# Avalon16.net
KiCad netlist of a schematic drawn in EAGLE
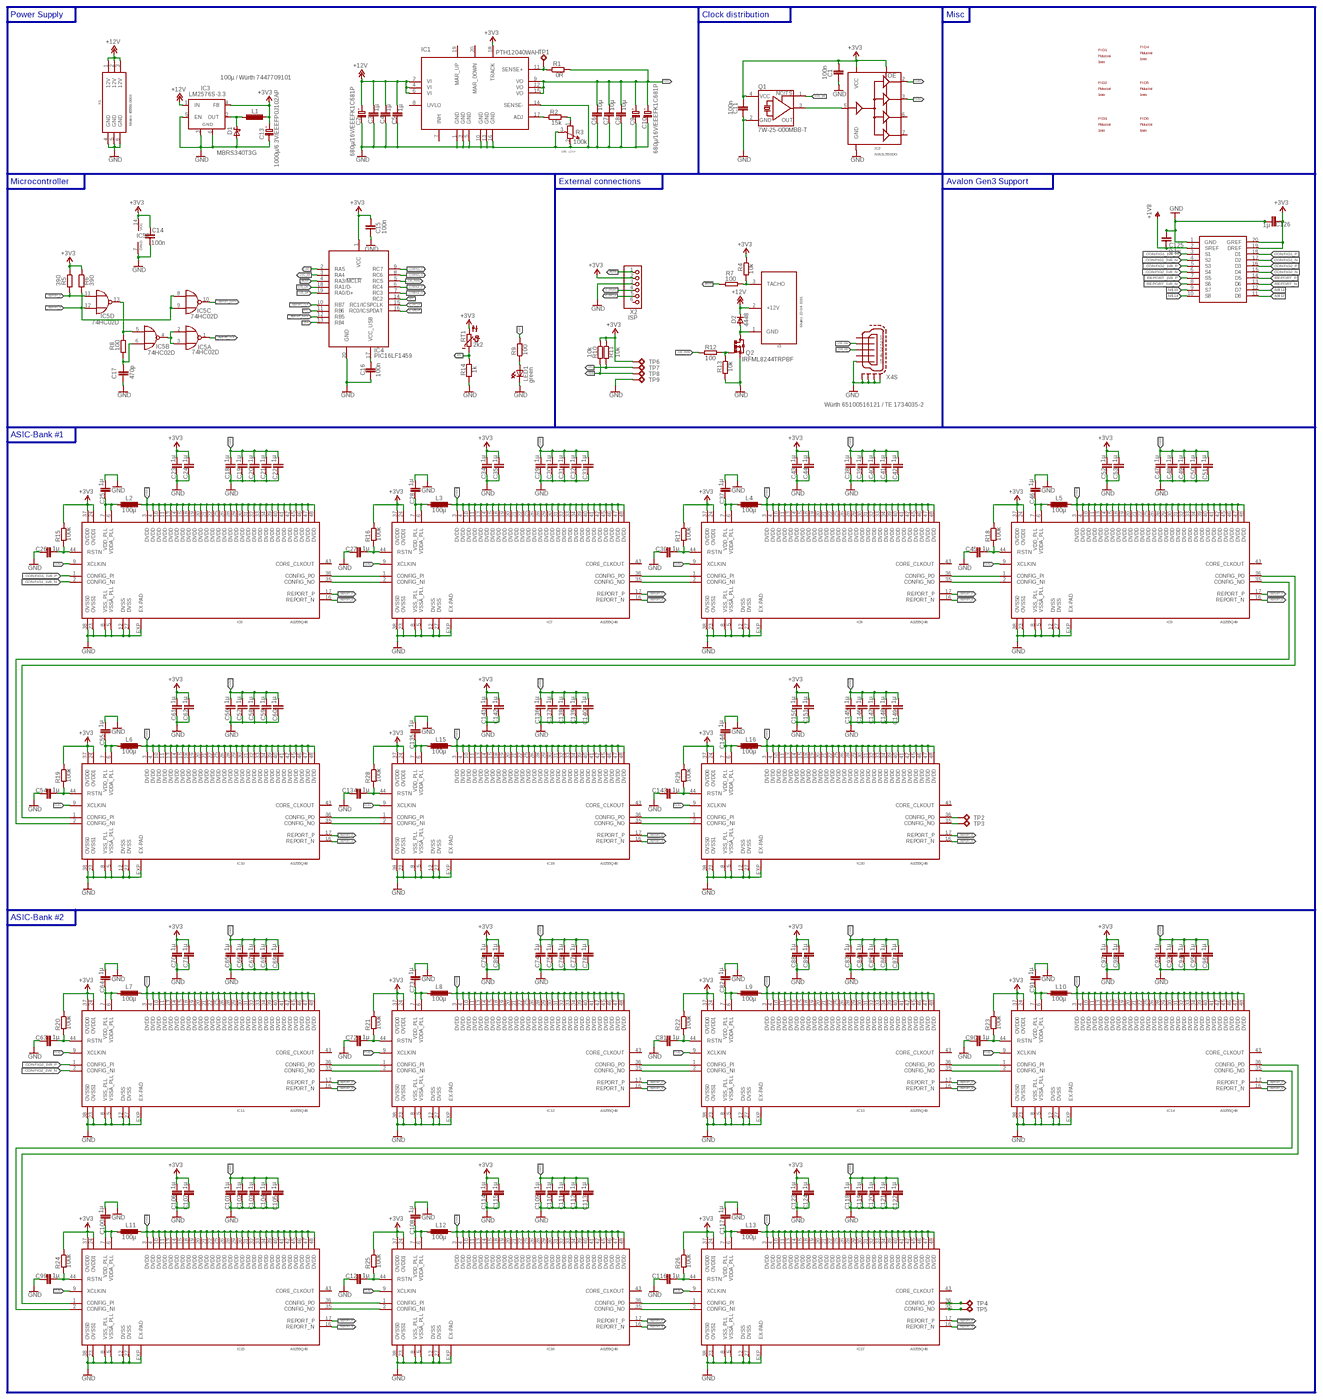
[diagram p0: schematic, sheet 1, overview]
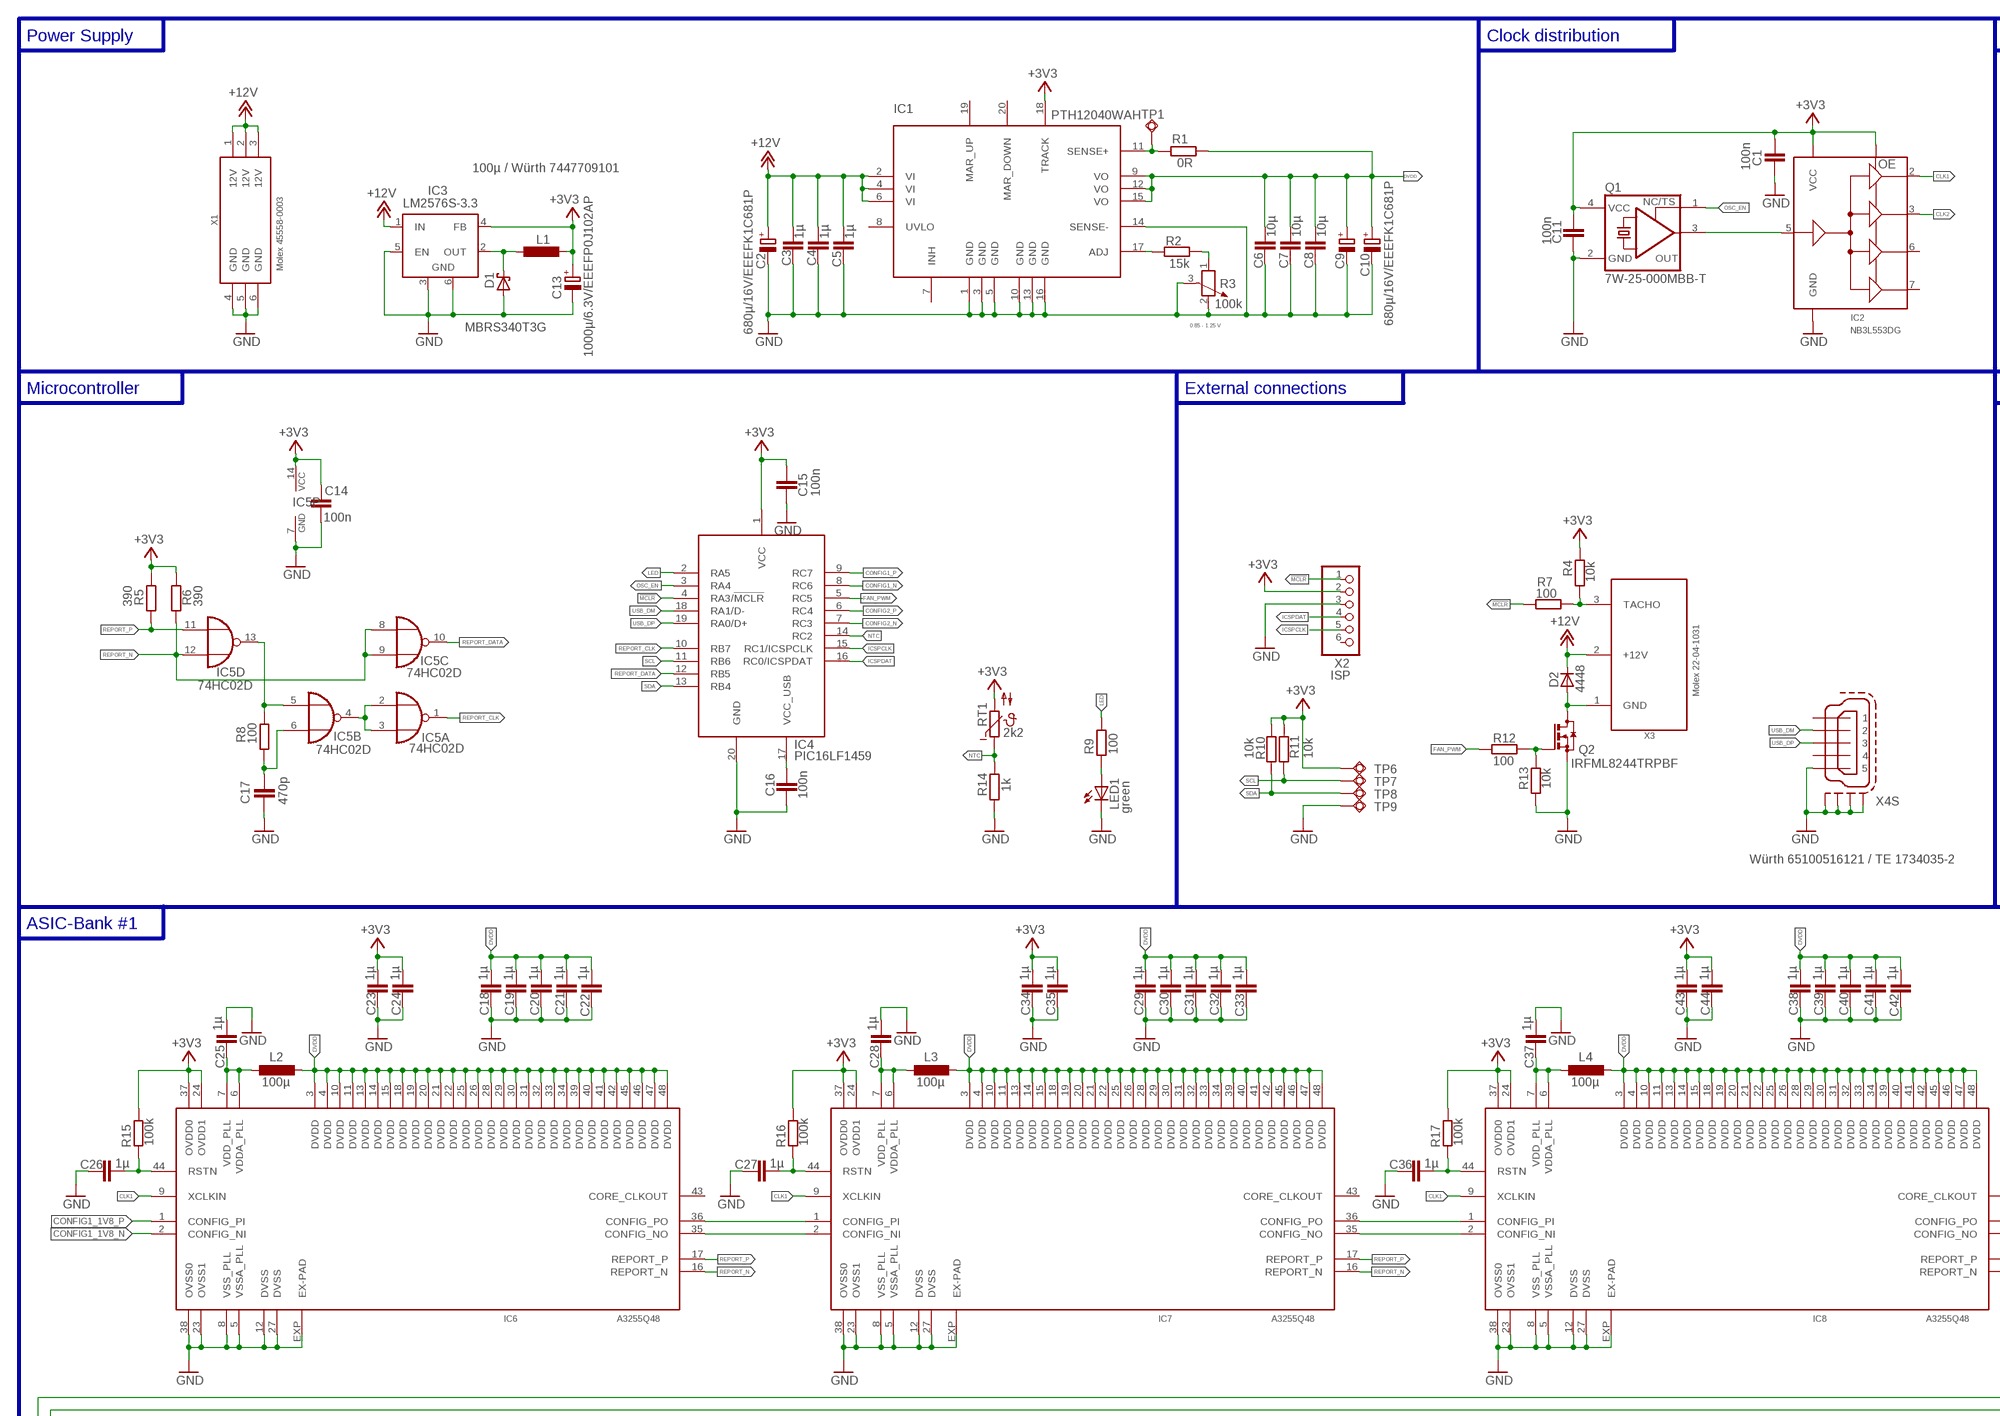
[diagram p1: schematic, sheet 1, part 1 of 4]
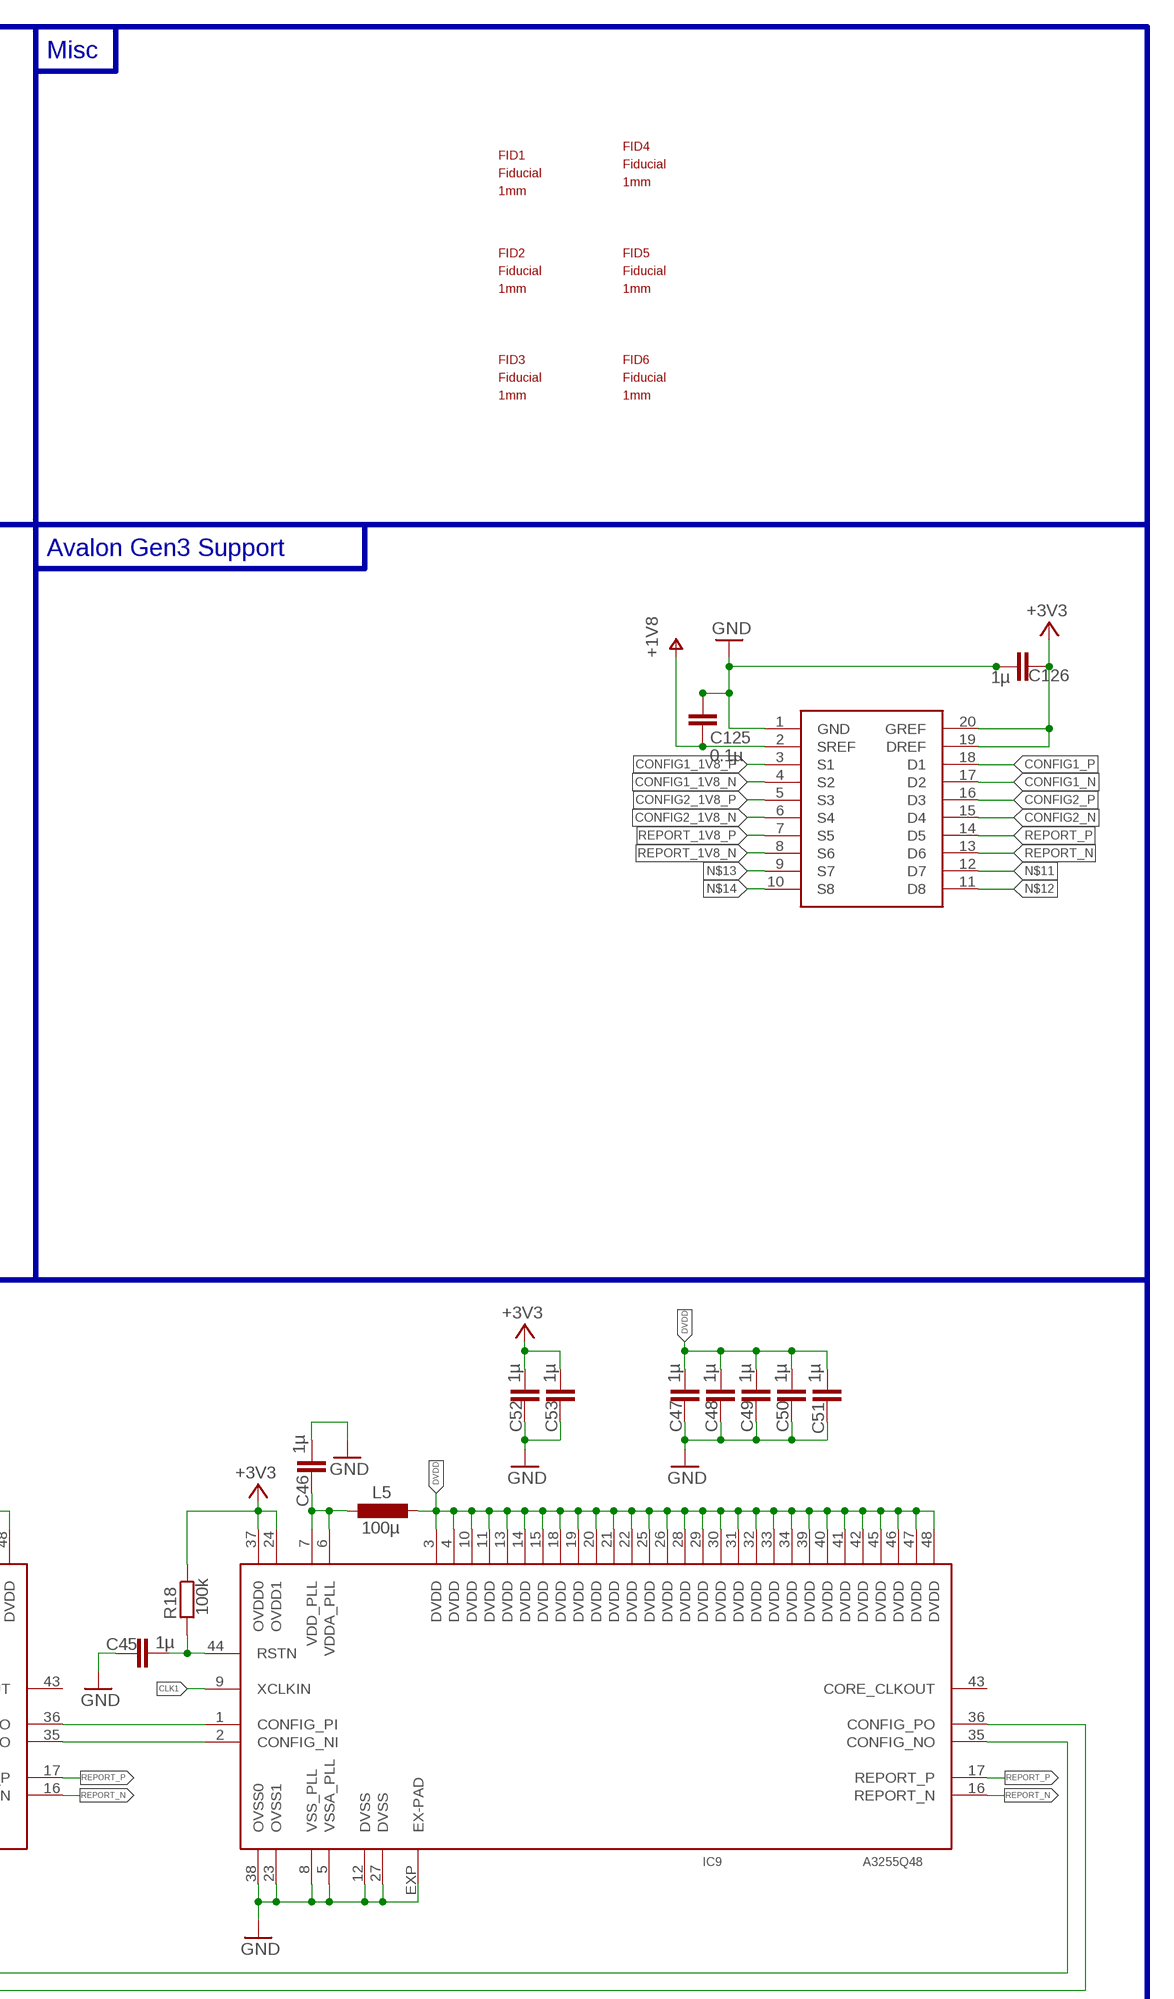
[diagram p2: schematic, sheet 1, part 2 of 4]
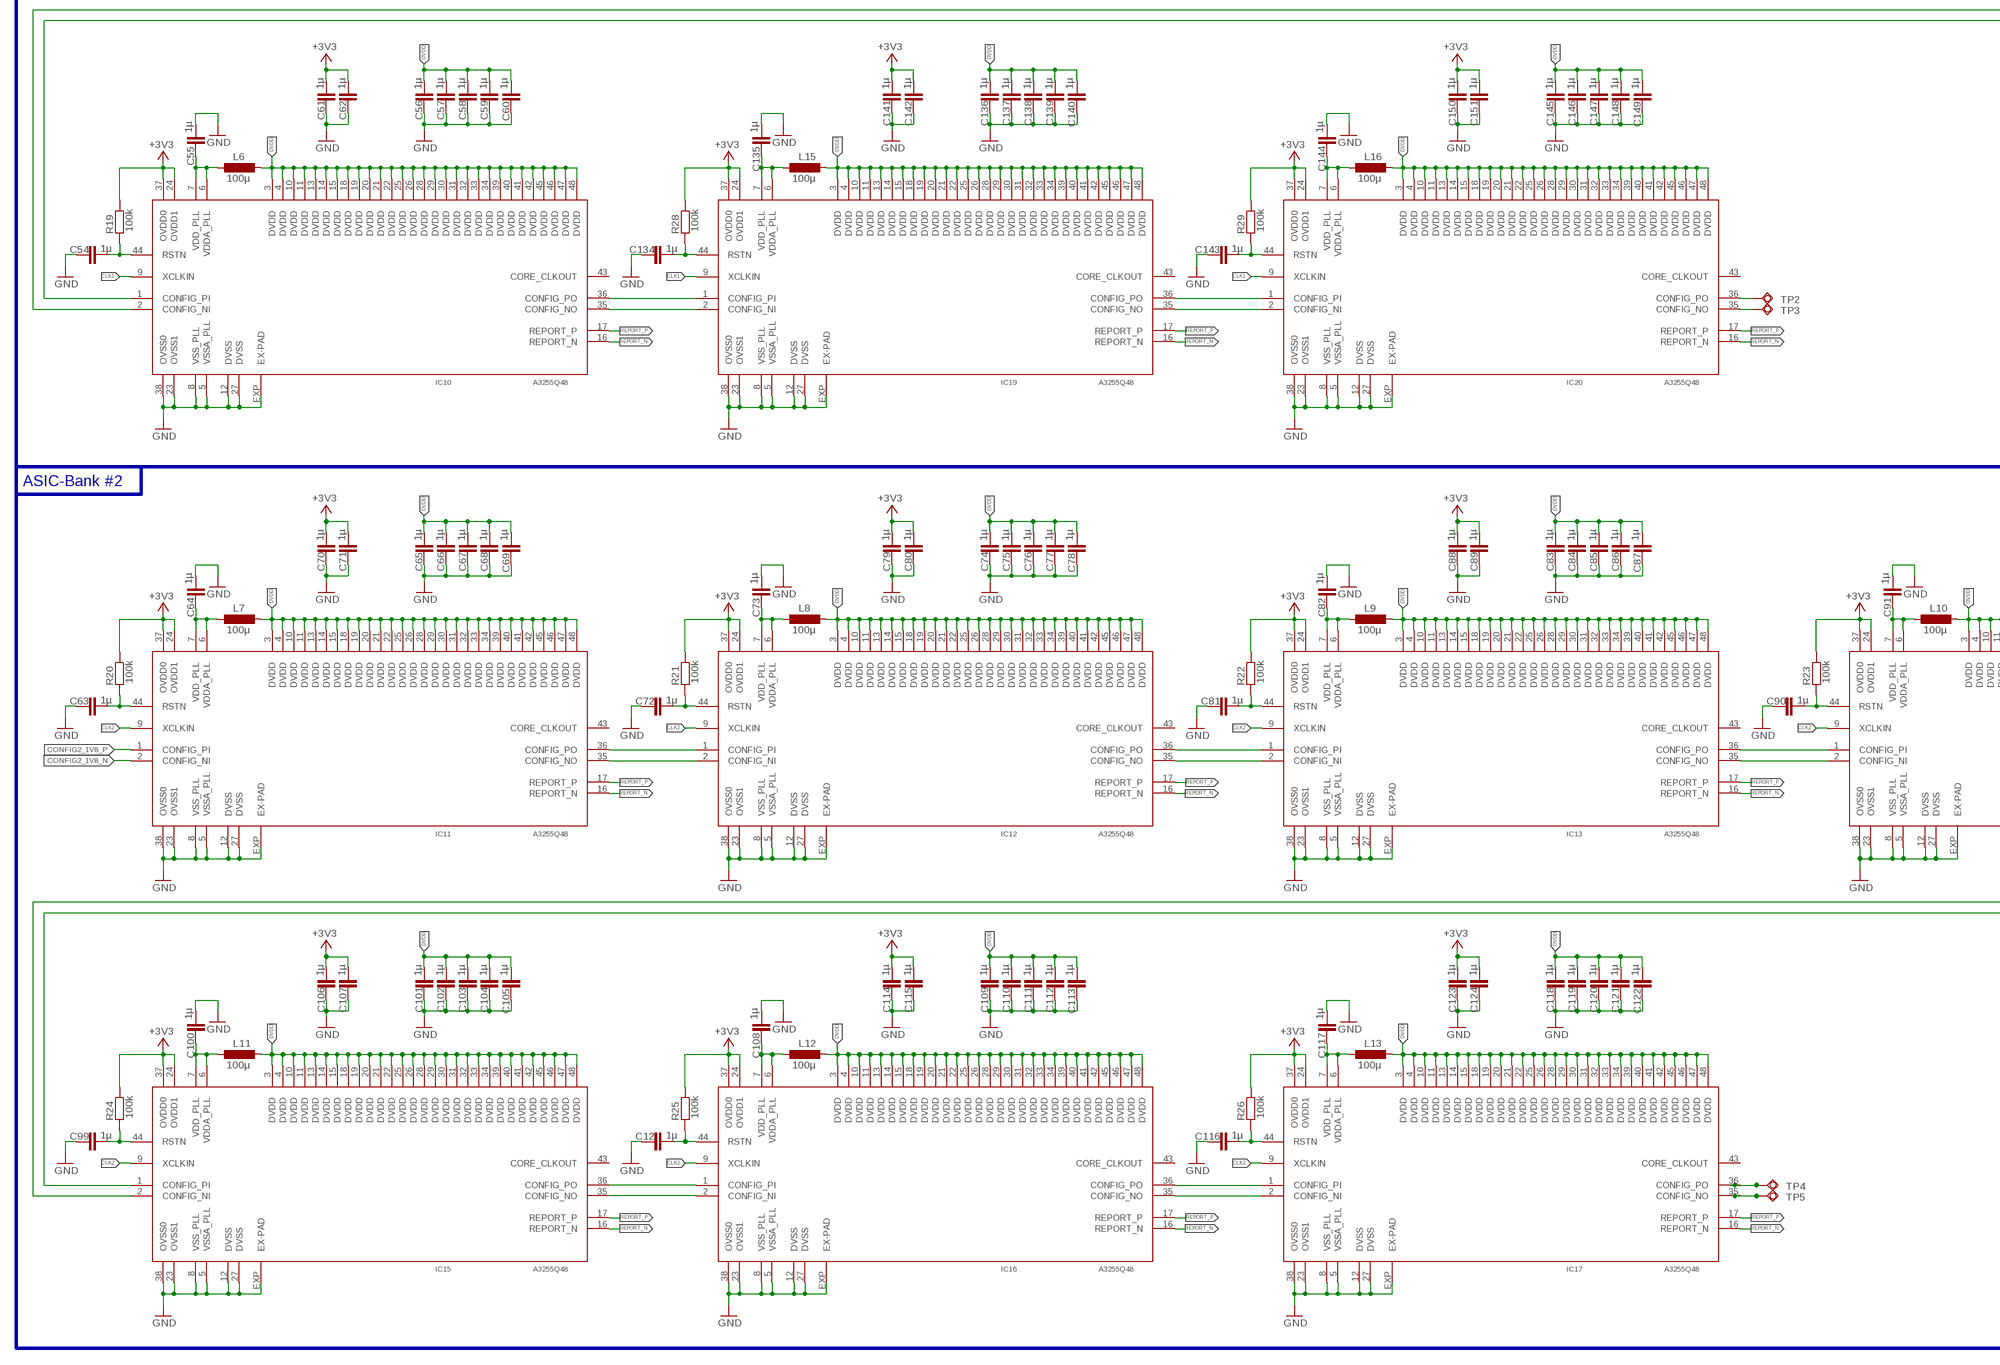
[diagram p3: schematic, sheet 1, part 3 of 4]
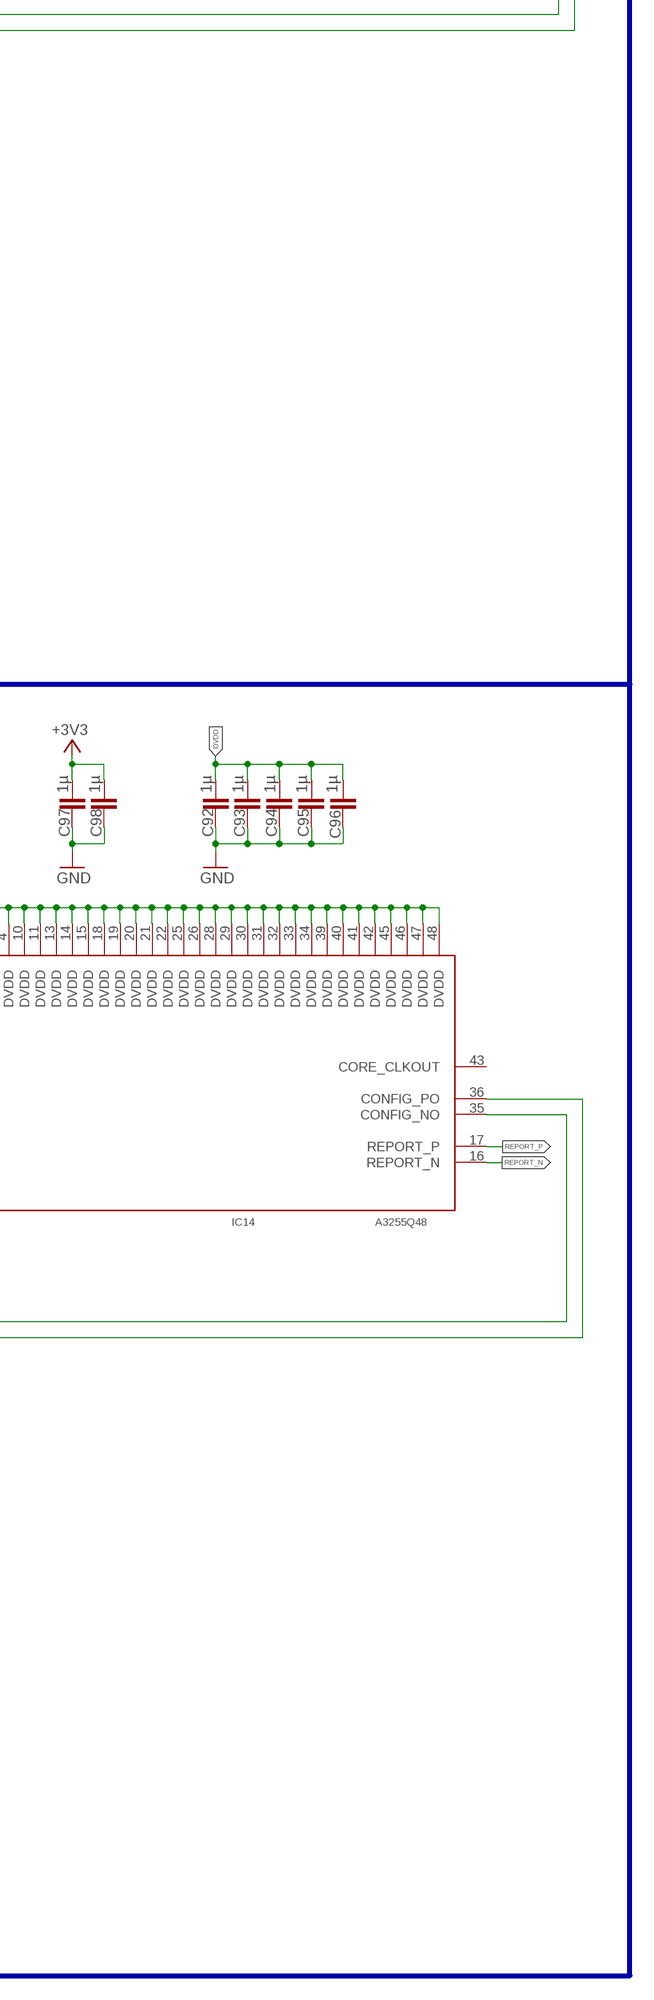
[diagram p4: schematic, sheet 1, part 4 of 4]

(export (version "E")
  (design (tool "Eeschema 10.0.6"))
  (components
    (comp (ref "C1")
      (value "100n")
      (footprint "eagle-import:C0805")
      (libsource (lib "eagle-import") (part "C-EUC0805"))
    )
    (comp (ref "C2")
      (value "680µ/16V/EEEFK1C681P")
      (footprint "eagle-import:PANASONIC_G")
      (libsource (lib "eagle-import") (part "CPOL-EUG"))
    )
    (comp (ref "C3")
      (value "1µ")
      (footprint "eagle-import:C0805")
      (libsource (lib "eagle-import") (part "C-EUC0805"))
    )
    (comp (ref "C4")
      (value "1µ")
      (footprint "eagle-import:C0805")
      (libsource (lib "eagle-import") (part "C-EUC0805"))
    )
    (comp (ref "C5")
      (value "1µ")
      (footprint "eagle-import:C0805")
      (libsource (lib "eagle-import") (part "C-EUC0805"))
    )
    (comp (ref "C6")
      (value "10µ")
      (footprint "eagle-import:C0805")
      (libsource (lib "eagle-import") (part "C-EUC0805"))
    )
    (comp (ref "C7")
      (value "10µ")
      (footprint "eagle-import:C0805")
      (libsource (lib "eagle-import") (part "C-EUC0805"))
    )
    (comp (ref "C8")
      (value "10µ")
      (footprint "eagle-import:C0805")
      (libsource (lib "eagle-import") (part "C-EUC0805"))
    )
    (comp (ref "C9")
      (value "680µ/16V/EEEFK1C681P")
      (footprint "eagle-import:PANASONIC_G")
      (libsource (lib "eagle-import") (part "CPOL-EUG"))
    )
    (comp (ref "C10")
      (value "680µ/16V/EEEFK1C681P")
      (footprint "eagle-import:PANASONIC_G")
      (libsource (lib "eagle-import") (part "CPOL-EUG"))
    )
    (comp (ref "C11")
      (value "100n")
      (footprint "eagle-import:C0805")
      (libsource (lib "eagle-import") (part "C-EUC0805"))
    )
    (comp (ref "C12")
      (value "1µ")
      (footprint "eagle-import:C0805")
      (libsource (lib "eagle-import") (part "C-EUC0805"))
    )
    (comp (ref "C13")
      (value "1000µ/6.3V/EEEFP0J102AP")
      (footprint "eagle-import:PANASONIC_F")
      (libsource (lib "eagle-import") (part "CPOL-EUF"))
    )
    (comp (ref "C14")
      (value "100n")
      (footprint "eagle-import:C0805")
      (libsource (lib "eagle-import") (part "C-EUC0805"))
    )
    (comp (ref "C15")
      (value "100n")
      (footprint "eagle-import:C0805")
      (libsource (lib "eagle-import") (part "C-EUC0805"))
    )
    (comp (ref "C16")
      (value "100n")
      (footprint "eagle-import:C0805")
      (libsource (lib "eagle-import") (part "C-EUC0805"))
    )
    (comp (ref "C17")
      (value "470p")
      (footprint "eagle-import:C0805")
      (libsource (lib "eagle-import") (part "C-EUC0805"))
    )
    (comp (ref "C18")
      (value "1µ")
      (footprint "eagle-import:C0805")
      (libsource (lib "eagle-import") (part "C-EUC0805"))
    )
    (comp (ref "C19")
      (value "1µ")
      (footprint "eagle-import:C0805")
      (libsource (lib "eagle-import") (part "C-EUC0805"))
    )
    (comp (ref "C20")
      (value "1µ")
      (footprint "eagle-import:C0805")
      (libsource (lib "eagle-import") (part "C-EUC0805"))
    )
    (comp (ref "C21")
      (value "1µ")
      (footprint "eagle-import:C0805")
      (libsource (lib "eagle-import") (part "C-EUC0805"))
    )
    (comp (ref "C22")
      (value "1µ")
      (footprint "eagle-import:C0805")
      (libsource (lib "eagle-import") (part "C-EUC0805"))
    )
    (comp (ref "C23")
      (value "1µ")
      (footprint "eagle-import:C0805")
      (libsource (lib "eagle-import") (part "C-EUC0805"))
    )
    (comp (ref "C24")
      (value "1µ")
      (footprint "eagle-import:C0805")
      (libsource (lib "eagle-import") (part "C-EUC0805"))
    )
    (comp (ref "C25")
      (value "1µ")
      (footprint "eagle-import:C0805")
      (libsource (lib "eagle-import") (part "C-EUC0805"))
    )
    (comp (ref "C26")
      (value "1µ")
      (footprint "eagle-import:C0805")
      (libsource (lib "eagle-import") (part "C-EUC0805"))
    )
    (comp (ref "C27")
      (value "1µ")
      (footprint "eagle-import:C0805")
      (libsource (lib "eagle-import") (part "C-EUC0805"))
    )
    (comp (ref "C28")
      (value "1µ")
      (footprint "eagle-import:C0805")
      (libsource (lib "eagle-import") (part "C-EUC0805"))
    )
    (comp (ref "C29")
      (value "1µ")
      (footprint "eagle-import:C0805")
      (libsource (lib "eagle-import") (part "C-EUC0805"))
    )
    (comp (ref "C30")
      (value "1µ")
      (footprint "eagle-import:C0805")
      (libsource (lib "eagle-import") (part "C-EUC0805"))
    )
    (comp (ref "C31")
      (value "1µ")
      (footprint "eagle-import:C0805")
      (libsource (lib "eagle-import") (part "C-EUC0805"))
    )
    (comp (ref "C32")
      (value "1µ")
      (footprint "eagle-import:C0805")
      (libsource (lib "eagle-import") (part "C-EUC0805"))
    )
    (comp (ref "C33")
      (value "1µ")
      (footprint "eagle-import:C0805")
      (libsource (lib "eagle-import") (part "C-EUC0805"))
    )
    (comp (ref "C34")
      (value "1µ")
      (footprint "eagle-import:C0805")
      (libsource (lib "eagle-import") (part "C-EUC0805"))
    )
    (comp (ref "C35")
      (value "1µ")
      (footprint "eagle-import:C0805")
      (libsource (lib "eagle-import") (part "C-EUC0805"))
    )
    (comp (ref "C36")
      (value "1µ")
      (footprint "eagle-import:C0805")
      (libsource (lib "eagle-import") (part "C-EUC0805"))
    )
    (comp (ref "C37")
      (value "1µ")
      (footprint "eagle-import:C0805")
      (libsource (lib "eagle-import") (part "C-EUC0805"))
    )
    (comp (ref "C38")
      (value "1µ")
      (footprint "eagle-import:C0805")
      (libsource (lib "eagle-import") (part "C-EUC0805"))
    )
    (comp (ref "C39")
      (value "1µ")
      (footprint "eagle-import:C0805")
      (libsource (lib "eagle-import") (part "C-EUC0805"))
    )
    (comp (ref "C40")
      (value "1µ")
      (footprint "eagle-import:C0805")
      (libsource (lib "eagle-import") (part "C-EUC0805"))
    )
    (comp (ref "C41")
      (value "1µ")
      (footprint "eagle-import:C0805")
      (libsource (lib "eagle-import") (part "C-EUC0805"))
    )
    (comp (ref "C42")
      (value "1µ")
      (footprint "eagle-import:C0805")
      (libsource (lib "eagle-import") (part "C-EUC0805"))
    )
    (comp (ref "C43")
      (value "1µ")
      (footprint "eagle-import:C0805")
      (libsource (lib "eagle-import") (part "C-EUC0805"))
    )
    (comp (ref "C44")
      (value "1µ")
      (footprint "eagle-import:C0805")
      (libsource (lib "eagle-import") (part "C-EUC0805"))
    )
    (comp (ref "C45")
      (value "1µ")
      (footprint "eagle-import:C0805")
      (libsource (lib "eagle-import") (part "C-EUC0805"))
    )
    (comp (ref "C46")
      (value "1µ")
      (footprint "eagle-import:C0805")
      (libsource (lib "eagle-import") (part "C-EUC0805"))
    )
    (comp (ref "C47")
      (value "1µ")
      (footprint "eagle-import:C0805")
      (libsource (lib "eagle-import") (part "C-EUC0805"))
    )
    (comp (ref "C48")
      (value "1µ")
      (footprint "eagle-import:C0805")
      (libsource (lib "eagle-import") (part "C-EUC0805"))
    )
    (comp (ref "C49")
      (value "1µ")
      (footprint "eagle-import:C0805")
      (libsource (lib "eagle-import") (part "C-EUC0805"))
    )
    (comp (ref "C50")
      (value "1µ")
      (footprint "eagle-import:C0805")
      (libsource (lib "eagle-import") (part "C-EUC0805"))
    )
    (comp (ref "C51")
      (value "1µ")
      (footprint "eagle-import:C0805")
      (libsource (lib "eagle-import") (part "C-EUC0805"))
    )
    (comp (ref "C52")
      (value "1µ")
      (footprint "eagle-import:C0805")
      (libsource (lib "eagle-import") (part "C-EUC0805"))
    )
    (comp (ref "C53")
      (value "1µ")
      (footprint "eagle-import:C0805")
      (libsource (lib "eagle-import") (part "C-EUC0805"))
    )
    (comp (ref "C54")
      (value "1µ")
      (footprint "eagle-import:C0805")
      (libsource (lib "eagle-import") (part "C-EUC0805"))
    )
    (comp (ref "C55")
      (value "1µ")
      (footprint "eagle-import:C0805")
      (libsource (lib "eagle-import") (part "C-EUC0805"))
    )
    (comp (ref "C56")
      (value "1µ")
      (footprint "eagle-import:C0805")
      (libsource (lib "eagle-import") (part "C-EUC0805"))
    )
    (comp (ref "C57")
      (value "1µ")
      (footprint "eagle-import:C0805")
      (libsource (lib "eagle-import") (part "C-EUC0805"))
    )
    (comp (ref "C58")
      (value "1µ")
      (footprint "eagle-import:C0805")
      (libsource (lib "eagle-import") (part "C-EUC0805"))
    )
    (comp (ref "C59")
      (value "1µ")
      (footprint "eagle-import:C0805")
      (libsource (lib "eagle-import") (part "C-EUC0805"))
    )
    (comp (ref "C60")
      (value "1µ")
      (footprint "eagle-import:C0805")
      (libsource (lib "eagle-import") (part "C-EUC0805"))
    )
    (comp (ref "C61")
      (value "1µ")
      (footprint "eagle-import:C0805")
      (libsource (lib "eagle-import") (part "C-EUC0805"))
    )
    (comp (ref "C62")
      (value "1µ")
      (footprint "eagle-import:C0805")
      (libsource (lib "eagle-import") (part "C-EUC0805"))
    )
    (comp (ref "C63")
      (value "1µ")
      (footprint "eagle-import:C0805")
      (libsource (lib "eagle-import") (part "C-EUC0805"))
    )
    (comp (ref "C64")
      (value "1µ")
      (footprint "eagle-import:C0805")
      (libsource (lib "eagle-import") (part "C-EUC0805"))
    )
    (comp (ref "C65")
      (value "1µ")
      (footprint "eagle-import:C0805")
      (libsource (lib "eagle-import") (part "C-EUC0805"))
    )
    (comp (ref "C66")
      (value "1µ")
      (footprint "eagle-import:C0805")
      (libsource (lib "eagle-import") (part "C-EUC0805"))
    )
    (comp (ref "C67")
      (value "1µ")
      (footprint "eagle-import:C0805")
      (libsource (lib "eagle-import") (part "C-EUC0805"))
    )
    (comp (ref "C68")
      (value "1µ")
      (footprint "eagle-import:C0805")
      (libsource (lib "eagle-import") (part "C-EUC0805"))
    )
    (comp (ref "C69")
      (value "1µ")
      (footprint "eagle-import:C0805")
      (libsource (lib "eagle-import") (part "C-EUC0805"))
    )
    (comp (ref "C70")
      (value "1µ")
      (footprint "eagle-import:C0805")
      (libsource (lib "eagle-import") (part "C-EUC0805"))
    )
    (comp (ref "C71")
      (value "1µ")
      (footprint "eagle-import:C0805")
      (libsource (lib "eagle-import") (part "C-EUC0805"))
    )
    (comp (ref "C72")
      (value "1µ")
      (footprint "eagle-import:C0805")
      (libsource (lib "eagle-import") (part "C-EUC0805"))
    )
    (comp (ref "C73")
      (value "1µ")
      (footprint "eagle-import:C0805")
      (libsource (lib "eagle-import") (part "C-EUC0805"))
    )
    (comp (ref "C74")
      (value "1µ")
      (footprint "eagle-import:C0805")
      (libsource (lib "eagle-import") (part "C-EUC0805"))
    )
    (comp (ref "C75")
      (value "1µ")
      (footprint "eagle-import:C0805")
      (libsource (lib "eagle-import") (part "C-EUC0805"))
    )
    (comp (ref "C76")
      (value "1µ")
      (footprint "eagle-import:C0805")
      (libsource (lib "eagle-import") (part "C-EUC0805"))
    )
    (comp (ref "C77")
      (value "1µ")
      (footprint "eagle-import:C0805")
      (libsource (lib "eagle-import") (part "C-EUC0805"))
    )
    (comp (ref "C78")
      (value "1µ")
      (footprint "eagle-import:C0805")
      (libsource (lib "eagle-import") (part "C-EUC0805"))
    )
    (comp (ref "C79")
      (value "1µ")
      (footprint "eagle-import:C0805")
      (libsource (lib "eagle-import") (part "C-EUC0805"))
    )
    (comp (ref "C80")
      (value "1µ")
      (footprint "eagle-import:C0805")
      (libsource (lib "eagle-import") (part "C-EUC0805"))
    )
    (comp (ref "C81")
      (value "1µ")
      (footprint "eagle-import:C0805")
      (libsource (lib "eagle-import") (part "C-EUC0805"))
    )
    (comp (ref "C82")
      (value "1µ")
      (footprint "eagle-import:C0805")
      (libsource (lib "eagle-import") (part "C-EUC0805"))
    )
    (comp (ref "C83")
      (value "1µ")
      (footprint "eagle-import:C0805")
      (libsource (lib "eagle-import") (part "C-EUC0805"))
    )
    (comp (ref "C84")
      (value "1µ")
      (footprint "eagle-import:C0805")
      (libsource (lib "eagle-import") (part "C-EUC0805"))
    )
    (comp (ref "C85")
      (value "1µ")
      (footprint "eagle-import:C0805")
      (libsource (lib "eagle-import") (part "C-EUC0805"))
    )
    (comp (ref "C86")
      (value "1µ")
      (footprint "eagle-import:C0805")
      (libsource (lib "eagle-import") (part "C-EUC0805"))
    )
    (comp (ref "C87")
      (value "1µ")
      (footprint "eagle-import:C0805")
      (libsource (lib "eagle-import") (part "C-EUC0805"))
    )
    (comp (ref "C88")
      (value "1µ")
      (footprint "eagle-import:C0805")
      (libsource (lib "eagle-import") (part "C-EUC0805"))
    )
    (comp (ref "C89")
      (value "1µ")
      (footprint "eagle-import:C0805")
      (libsource (lib "eagle-import") (part "C-EUC0805"))
    )
    (comp (ref "C90")
      (value "1µ")
      (footprint "eagle-import:C0805")
      (libsource (lib "eagle-import") (part "C-EUC0805"))
    )
    (comp (ref "C91")
      (value "1µ")
      (footprint "eagle-import:C0805")
      (libsource (lib "eagle-import") (part "C-EUC0805"))
    )
    (comp (ref "C92")
      (value "1µ")
      (footprint "eagle-import:C0805")
      (libsource (lib "eagle-import") (part "C-EUC0805"))
    )
    (comp (ref "C93")
      (value "1µ")
      (footprint "eagle-import:C0805")
      (libsource (lib "eagle-import") (part "C-EUC0805"))
    )
    (comp (ref "C94")
      (value "1µ")
      (footprint "eagle-import:C0805")
      (libsource (lib "eagle-import") (part "C-EUC0805"))
    )
    (comp (ref "C95")
      (value "1µ")
      (footprint "eagle-import:C0805")
      (libsource (lib "eagle-import") (part "C-EUC0805"))
    )
    (comp (ref "C96")
      (value "1µ")
      (footprint "eagle-import:C0805")
      (libsource (lib "eagle-import") (part "C-EUC0805"))
    )
    (comp (ref "C97")
      (value "1µ")
      (footprint "eagle-import:C0805")
      (libsource (lib "eagle-import") (part "C-EUC0805"))
    )
    (comp (ref "C98")
      (value "1µ")
      (footprint "eagle-import:C0805")
      (libsource (lib "eagle-import") (part "C-EUC0805"))
    )
    (comp (ref "C99")
      (value "1µ")
      (footprint "eagle-import:C0805")
      (libsource (lib "eagle-import") (part "C-EUC0805"))
    )
    (comp (ref "C100")
      (value "1µ")
      (footprint "eagle-import:C0805")
      (libsource (lib "eagle-import") (part "C-EUC0805"))
    )
    (comp (ref "C101")
      (value "1µ")
      (footprint "eagle-import:C0805")
      (libsource (lib "eagle-import") (part "C-EUC0805"))
    )
    (comp (ref "C102")
      (value "1µ")
      (footprint "eagle-import:C0805")
      (libsource (lib "eagle-import") (part "C-EUC0805"))
    )
    (comp (ref "C103")
      (value "1µ")
      (footprint "eagle-import:C0805")
      (libsource (lib "eagle-import") (part "C-EUC0805"))
    )
    (comp (ref "C104")
      (value "1µ")
      (footprint "eagle-import:C0805")
      (libsource (lib "eagle-import") (part "C-EUC0805"))
    )
    (comp (ref "C105")
      (value "1µ")
      (footprint "eagle-import:C0805")
      (libsource (lib "eagle-import") (part "C-EUC0805"))
    )
    (comp (ref "C106")
      (value "1µ")
      (footprint "eagle-import:C0805")
      (libsource (lib "eagle-import") (part "C-EUC0805"))
    )
    (comp (ref "C107")
      (value "1µ")
      (footprint "eagle-import:C0805")
      (libsource (lib "eagle-import") (part "C-EUC0805"))
    )
    (comp (ref "C108")
      (value "1µ")
      (footprint "eagle-import:C0805")
      (libsource (lib "eagle-import") (part "C-EUC0805"))
    )
    (comp (ref "C109")
      (value "1µ")
      (footprint "eagle-import:C0805")
      (libsource (lib "eagle-import") (part "C-EUC0805"))
    )
    (comp (ref "C110")
      (value "1µ")
      (footprint "eagle-import:C0805")
      (libsource (lib "eagle-import") (part "C-EUC0805"))
    )
    (comp (ref "C111")
      (value "1µ")
      (footprint "eagle-import:C0805")
      (libsource (lib "eagle-import") (part "C-EUC0805"))
    )
    (comp (ref "C112")
      (value "1µ")
      (footprint "eagle-import:C0805")
      (libsource (lib "eagle-import") (part "C-EUC0805"))
    )
    (comp (ref "C113")
      (value "1µ")
      (footprint "eagle-import:C0805")
      (libsource (lib "eagle-import") (part "C-EUC0805"))
    )
    (comp (ref "C114")
      (value "1µ")
      (footprint "eagle-import:C0805")
      (libsource (lib "eagle-import") (part "C-EUC0805"))
    )
    (comp (ref "C115")
      (value "1µ")
      (footprint "eagle-import:C0805")
      (libsource (lib "eagle-import") (part "C-EUC0805"))
    )
    (comp (ref "C116")
      (value "1µ")
      (footprint "eagle-import:C0805")
      (libsource (lib "eagle-import") (part "C-EUC0805"))
    )
    (comp (ref "C117")
      (value "1µ")
      (footprint "eagle-import:C0805")
      (libsource (lib "eagle-import") (part "C-EUC0805"))
    )
    (comp (ref "C118")
      (value "1µ")
      (footprint "eagle-import:C0805")
      (libsource (lib "eagle-import") (part "C-EUC0805"))
    )
    (comp (ref "C119")
      (value "1µ")
      (footprint "eagle-import:C0805")
      (libsource (lib "eagle-import") (part "C-EUC0805"))
    )
    (comp (ref "C120")
      (value "1µ")
      (footprint "eagle-import:C0805")
      (libsource (lib "eagle-import") (part "C-EUC0805"))
    )
    (comp (ref "C121")
      (value "1µ")
      (footprint "eagle-import:C0805")
      (libsource (lib "eagle-import") (part "C-EUC0805"))
    )
    (comp (ref "C122")
      (value "1µ")
      (footprint "eagle-import:C0805")
      (libsource (lib "eagle-import") (part "C-EUC0805"))
    )
    (comp (ref "C123")
      (value "1µ")
      (footprint "eagle-import:C0805")
      (libsource (lib "eagle-import") (part "C-EUC0805"))
    )
    (comp (ref "C124")
      (value "1µ")
      (footprint "eagle-import:C0805")
      (libsource (lib "eagle-import") (part "C-EUC0805"))
    )
    (comp (ref "C125")
      (value "0.1µ")
      (footprint "eagle-import:C0805")
      (libsource (lib "eagle-import") (part "C-EUC0805"))
    )
    (comp (ref "C126")
      (value "1µ")
      (footprint "eagle-import:C0805")
      (libsource (lib "eagle-import") (part "C-EUC0805"))
    )
    (comp (ref "C134")
      (value "1µ")
      (footprint "eagle-import:C0805")
      (libsource (lib "eagle-import") (part "C-EUC0805"))
    )
    (comp (ref "C135")
      (value "1µ")
      (footprint "eagle-import:C0805")
      (libsource (lib "eagle-import") (part "C-EUC0805"))
    )
    (comp (ref "C136")
      (value "1µ")
      (footprint "eagle-import:C0805")
      (libsource (lib "eagle-import") (part "C-EUC0805"))
    )
    (comp (ref "C137")
      (value "1µ")
      (footprint "eagle-import:C0805")
      (libsource (lib "eagle-import") (part "C-EUC0805"))
    )
    (comp (ref "C138")
      (value "1µ")
      (footprint "eagle-import:C0805")
      (libsource (lib "eagle-import") (part "C-EUC0805"))
    )
    (comp (ref "C139")
      (value "1µ")
      (footprint "eagle-import:C0805")
      (libsource (lib "eagle-import") (part "C-EUC0805"))
    )
    (comp (ref "C140")
      (value "1µ")
      (footprint "eagle-import:C0805")
      (libsource (lib "eagle-import") (part "C-EUC0805"))
    )
    (comp (ref "C141")
      (value "1µ")
      (footprint "eagle-import:C0805")
      (libsource (lib "eagle-import") (part "C-EUC0805"))
    )
    (comp (ref "C142")
      (value "1µ")
      (footprint "eagle-import:C0805")
      (libsource (lib "eagle-import") (part "C-EUC0805"))
    )
    (comp (ref "C143")
      (value "1µ")
      (footprint "eagle-import:C0805")
      (libsource (lib "eagle-import") (part "C-EUC0805"))
    )
    (comp (ref "C144")
      (value "1µ")
      (footprint "eagle-import:C0805")
      (libsource (lib "eagle-import") (part "C-EUC0805"))
    )
    (comp (ref "C145")
      (value "1µ")
      (footprint "eagle-import:C0805")
      (libsource (lib "eagle-import") (part "C-EUC0805"))
    )
    (comp (ref "C146")
      (value "1µ")
      (footprint "eagle-import:C0805")
      (libsource (lib "eagle-import") (part "C-EUC0805"))
    )
    (comp (ref "C147")
      (value "1µ")
      (footprint "eagle-import:C0805")
      (libsource (lib "eagle-import") (part "C-EUC0805"))
    )
    (comp (ref "C148")
      (value "1µ")
      (footprint "eagle-import:C0805")
      (libsource (lib "eagle-import") (part "C-EUC0805"))
    )
    (comp (ref "C149")
      (value "1µ")
      (footprint "eagle-import:C0805")
      (libsource (lib "eagle-import") (part "C-EUC0805"))
    )
    (comp (ref "C150")
      (value "1µ")
      (footprint "eagle-import:C0805")
      (libsource (lib "eagle-import") (part "C-EUC0805"))
    )
    (comp (ref "C151")
      (value "1µ")
      (footprint "eagle-import:C0805")
      (libsource (lib "eagle-import") (part "C-EUC0805"))
    )
    (comp (ref "D1")
      (value "MBRS340T3G")
      (footprint "eagle-import:SMC")
      (libsource (lib "eagle-import") (part "SCHOTTKY-DIODESMC"))
    )
    (comp (ref "D2")
      (value "4448")
      (footprint "eagle-import:SOD80C")
      (libsource (lib "eagle-import") (part "PMLL41SOD80C"))
    )
    (comp (ref "FID1")
      (value "1mm")
      (footprint "eagle-import:FIDUCIAL")
      (libsource (lib "eagle-import") (part "FIDUCIAL"))
    )
    (comp (ref "FID2")
      (value "1mm")
      (footprint "eagle-import:FIDUCIAL")
      (libsource (lib "eagle-import") (part "FIDUCIAL"))
    )
    (comp (ref "FID3")
      (value "1mm")
      (footprint "eagle-import:FIDUCIAL")
      (libsource (lib "eagle-import") (part "FIDUCIAL"))
    )
    (comp (ref "FID4")
      (value "1mm")
      (footprint "eagle-import:FIDUCIAL")
      (libsource (lib "eagle-import") (part "FIDUCIAL"))
    )
    (comp (ref "FID5")
      (value "1mm")
      (footprint "eagle-import:FIDUCIAL")
      (libsource (lib "eagle-import") (part "FIDUCIAL"))
    )
    (comp (ref "FID6")
      (value "1mm")
      (footprint "eagle-import:FIDUCIAL")
      (libsource (lib "eagle-import") (part "FIDUCIAL"))
    )
    (comp (ref "IC1")
      (value "PTH12040WAH")
      (footprint "eagle-import:PTH12040WAH")
      (libsource (lib "eagle-import") (part "PTH12040WAH"))
    )
    (comp (ref "IC2")
      (value "NB3L553DG")
      (footprint "eagle-import:SO8")
      (libsource (lib "eagle-import") (part "NB3L553"))
    )
    (comp (ref "IC3")
      (value "LM2576S-3.3")
      (footprint "eagle-import:TO263-5")
      (libsource (lib "eagle-import") (part "LM2596S"))
    )
    (comp (ref "IC4")
      (value "PIC16LF1459")
      (footprint "eagle-import:SOIC20")
      (libsource (lib "eagle-import") (part "PIC16LF1459"))
    )
    (comp (ref "IC5")
      (value "74HC02D")
      (footprint "eagle-import:SO14")
      (libsource (lib "eagle-import") (part "7402DHC"))
    )
    (comp (ref "IC6")
      (value "A3255Q48")
      (footprint "eagle-import:QFN48")
      (libsource (lib "eagle-import") (part "A3255"))
    )
    (comp (ref "IC7")
      (value "A3255Q48")
      (footprint "eagle-import:QFN48")
      (libsource (lib "eagle-import") (part "A3255"))
    )
    (comp (ref "IC8")
      (value "A3255Q48")
      (footprint "eagle-import:QFN48")
      (libsource (lib "eagle-import") (part "A3255"))
    )
    (comp (ref "IC9")
      (value "A3255Q48")
      (footprint "eagle-import:QFN48")
      (libsource (lib "eagle-import") (part "A3255"))
    )
    (comp (ref "IC10")
      (value "A3255Q48")
      (footprint "eagle-import:QFN48")
      (libsource (lib "eagle-import") (part "A3255"))
    )
    (comp (ref "IC11")
      (value "A3255Q48")
      (footprint "eagle-import:QFN48")
      (libsource (lib "eagle-import") (part "A3255"))
    )
    (comp (ref "IC12")
      (value "A3255Q48")
      (footprint "eagle-import:QFN48")
      (libsource (lib "eagle-import") (part "A3255"))
    )
    (comp (ref "IC13")
      (value "A3255Q48")
      (footprint "eagle-import:QFN48")
      (libsource (lib "eagle-import") (part "A3255"))
    )
    (comp (ref "IC14")
      (value "A3255Q48")
      (footprint "eagle-import:QFN48")
      (libsource (lib "eagle-import") (part "A3255"))
    )
    (comp (ref "IC15")
      (value "A3255Q48")
      (footprint "eagle-import:QFN48")
      (libsource (lib "eagle-import") (part "A3255"))
    )
    (comp (ref "IC16")
      (value "A3255Q48")
      (footprint "eagle-import:QFN48")
      (libsource (lib "eagle-import") (part "A3255"))
    )
    (comp (ref "IC17")
      (value "A3255Q48")
      (footprint "eagle-import:QFN48")
      (libsource (lib "eagle-import") (part "A3255"))
    )
    (comp (ref "IC19")
      (value "A3255Q48")
      (footprint "eagle-import:QFN48")
      (libsource (lib "eagle-import") (part "A3255"))
    )
    (comp (ref "IC20")
      (value "A3255Q48")
      (footprint "eagle-import:QFN48")
      (libsource (lib "eagle-import") (part "A3255"))
    )
    (comp (ref "L1")
      (value "100µ / Würth 7447709101")
      (footprint "eagle-import:WUERTH-7447709101")
      (libsource (lib "eagle-import") (part "WUERTH-7447709101"))
    )
    (comp (ref "L2")
      (value "100µ")
      (footprint "eagle-import:L0805")
      (libsource (lib "eagle-import") (part "L-EUL0805"))
    )
    (comp (ref "L3")
      (value "100µ")
      (footprint "eagle-import:L0805")
      (libsource (lib "eagle-import") (part "L-EUL0805"))
    )
    (comp (ref "L4")
      (value "100µ")
      (footprint "eagle-import:L0805")
      (libsource (lib "eagle-import") (part "L-EUL0805"))
    )
    (comp (ref "L5")
      (value "100µ")
      (footprint "eagle-import:L0805")
      (libsource (lib "eagle-import") (part "L-EUL0805"))
    )
    (comp (ref "L6")
      (value "100µ")
      (footprint "eagle-import:L0805")
      (libsource (lib "eagle-import") (part "L-EUL0805"))
    )
    (comp (ref "L7")
      (value "100µ")
      (footprint "eagle-import:L0805")
      (libsource (lib "eagle-import") (part "L-EUL0805"))
    )
    (comp (ref "L8")
      (value "100µ")
      (footprint "eagle-import:L0805")
      (libsource (lib "eagle-import") (part "L-EUL0805"))
    )
    (comp (ref "L9")
      (value "100µ")
      (footprint "eagle-import:L0805")
      (libsource (lib "eagle-import") (part "L-EUL0805"))
    )
    (comp (ref "L10")
      (value "100µ")
      (footprint "eagle-import:L0805")
      (libsource (lib "eagle-import") (part "L-EUL0805"))
    )
    (comp (ref "L11")
      (value "100µ")
      (footprint "eagle-import:L0805")
      (libsource (lib "eagle-import") (part "L-EUL0805"))
    )
    (comp (ref "L12")
      (value "100µ")
      (footprint "eagle-import:L0805")
      (libsource (lib "eagle-import") (part "L-EUL0805"))
    )
    (comp (ref "L13")
      (value "100µ")
      (footprint "eagle-import:L0805")
      (libsource (lib "eagle-import") (part "L-EUL0805"))
    )
    (comp (ref "L15")
      (value "100µ")
      (footprint "eagle-import:L0805")
      (libsource (lib "eagle-import") (part "L-EUL0805"))
    )
    (comp (ref "L16")
      (value "100µ")
      (footprint "eagle-import:L0805")
      (libsource (lib "eagle-import") (part "L-EUL0805"))
    )
    (comp (ref "LED1")
      (value "green")
      (footprint "eagle-import:SML0805")
      (libsource (lib "eagle-import") (part "LEDSML0805"))
    )
    (comp (ref "Q1")
      (value "7W-25-000MBB-T")
      (footprint "eagle-import:7W")
      (libsource (lib "eagle-import") (part "7W"))
    )
    (comp (ref "Q2")
      (value "IRFML8244TRPBF")
      (footprint "eagle-import:SOT23")
      (libsource (lib "eagle-import") (part "BSS123"))
    )
    (comp (ref "R1")
      (value "0R")
      (footprint "eagle-import:R0805")
      (libsource (lib "eagle-import") (part "R-EU_R0805"))
    )
    (comp (ref "R2")
      (value "15k")
      (footprint "eagle-import:R0805")
      (libsource (lib "eagle-import") (part "R-EU_R0805"))
    )
    (comp (ref "R3")
      (value "100k")
      (footprint "eagle-import:PT-SPIN")
      (libsource (lib "eagle-import") (part "POTENTIOMETER_PT_SPIN"))
    )
    (comp (ref "R4")
      (value "10k")
      (footprint "eagle-import:R0805")
      (libsource (lib "eagle-import") (part "R-EU_R0805"))
    )
    (comp (ref "R5")
      (value "390")
      (footprint "eagle-import:R0805")
      (libsource (lib "eagle-import") (part "R-EU_R0805"))
    )
    (comp (ref "R6")
      (value "390")
      (footprint "eagle-import:R0805")
      (libsource (lib "eagle-import") (part "R-EU_R0805"))
    )
    (comp (ref "R7")
      (value "100")
      (footprint "eagle-import:R0805")
      (libsource (lib "eagle-import") (part "R-EU_R0805"))
    )
    (comp (ref "R8")
      (value "100")
      (footprint "eagle-import:R0805")
      (libsource (lib "eagle-import") (part "R-EU_R0805"))
    )
    (comp (ref "R9")
      (value "100")
      (footprint "eagle-import:R0805")
      (libsource (lib "eagle-import") (part "R-EU_R0805"))
    )
    (comp (ref "R10")
      (value "10k")
      (footprint "eagle-import:R0805")
      (libsource (lib "eagle-import") (part "R-EU_R0805"))
    )
    (comp (ref "R11")
      (value "10k")
      (footprint "eagle-import:R0805")
      (libsource (lib "eagle-import") (part "R-EU_R0805"))
    )
    (comp (ref "R12")
      (value "100")
      (footprint "eagle-import:R0805")
      (libsource (lib "eagle-import") (part "R-EU_R0805"))
    )
    (comp (ref "R13")
      (value "10k")
      (footprint "eagle-import:R0805")
      (libsource (lib "eagle-import") (part "R-EU_R0805"))
    )
    (comp (ref "R14")
      (value "1k")
      (footprint "eagle-import:R0805")
      (libsource (lib "eagle-import") (part "R-EU_R0805"))
    )
    (comp (ref "R15")
      (value "100k")
      (footprint "eagle-import:R0805")
      (libsource (lib "eagle-import") (part "R-EU_R0805"))
    )
    (comp (ref "R16")
      (value "100k")
      (footprint "eagle-import:R0805")
      (libsource (lib "eagle-import") (part "R-EU_R0805"))
    )
    (comp (ref "R17")
      (value "100k")
      (footprint "eagle-import:R0805")
      (libsource (lib "eagle-import") (part "R-EU_R0805"))
    )
    (comp (ref "R18")
      (value "100k")
      (footprint "eagle-import:R0805")
      (libsource (lib "eagle-import") (part "R-EU_R0805"))
    )
    (comp (ref "R19")
      (value "100k")
      (footprint "eagle-import:R0805")
      (libsource (lib "eagle-import") (part "R-EU_R0805"))
    )
    (comp (ref "R20")
      (value "100k")
      (footprint "eagle-import:R0805")
      (libsource (lib "eagle-import") (part "R-EU_R0805"))
    )
    (comp (ref "R21")
      (value "100k")
      (footprint "eagle-import:R0805")
      (libsource (lib "eagle-import") (part "R-EU_R0805"))
    )
    (comp (ref "R22")
      (value "100k")
      (footprint "eagle-import:R0805")
      (libsource (lib "eagle-import") (part "R-EU_R0805"))
    )
    (comp (ref "R23")
      (value "100k")
      (footprint "eagle-import:R0805")
      (libsource (lib "eagle-import") (part "R-EU_R0805"))
    )
    (comp (ref "R24")
      (value "100k")
      (footprint "eagle-import:R0805")
      (libsource (lib "eagle-import") (part "R-EU_R0805"))
    )
    (comp (ref "R25")
      (value "100k")
      (footprint "eagle-import:R0805")
      (libsource (lib "eagle-import") (part "R-EU_R0805"))
    )
    (comp (ref "R26")
      (value "100k")
      (footprint "eagle-import:R0805")
      (libsource (lib "eagle-import") (part "R-EU_R0805"))
    )
    (comp (ref "R28")
      (value "100k")
      (footprint "eagle-import:R0805")
      (libsource (lib "eagle-import") (part "R-EU_R0805"))
    )
    (comp (ref "R29")
      (value "100k")
      (footprint "eagle-import:R0805")
      (libsource (lib "eagle-import") (part "R-EU_R0805"))
    )
    (comp (ref "RT1")
      (value "2k2")
      (footprint "eagle-import:0805")
      (libsource (lib "eagle-import") (part "NTC"))
    )
    (comp (ref "TP1")
      (value "TPSQTP20SQ")
      (footprint "eagle-import:TP20SQ")
      (libsource (lib "eagle-import") (part "TPSQTP20SQ"))
    )
    (comp (ref "TP2")
      (value "TPSQTP10SQ")
      (footprint "eagle-import:TP10SQ")
      (libsource (lib "eagle-import") (part "TPSQTP10SQ"))
    )
    (comp (ref "TP3")
      (value "TPSQTP10SQ")
      (footprint "eagle-import:TP10SQ")
      (libsource (lib "eagle-import") (part "TPSQTP10SQ"))
    )
    (comp (ref "TP4")
      (value "TPSQTP10SQ")
      (footprint "eagle-import:TP10SQ")
      (libsource (lib "eagle-import") (part "TPSQTP10SQ"))
    )
    (comp (ref "TP5")
      (value "TPSQTP10SQ")
      (footprint "eagle-import:TP10SQ")
      (libsource (lib "eagle-import") (part "TPSQTP10SQ"))
    )
    (comp (ref "TP6")
      (value "TPSQTP10SQ")
      (footprint "eagle-import:TP10SQ")
      (libsource (lib "eagle-import") (part "TPSQTP10SQ"))
    )
    (comp (ref "TP7")
      (value "TPSQTP10SQ")
      (footprint "eagle-import:TP10SQ")
      (libsource (lib "eagle-import") (part "TPSQTP10SQ"))
    )
    (comp (ref "TP8")
      (value "TPSQTP10SQ")
      (footprint "eagle-import:TP10SQ")
      (libsource (lib "eagle-import") (part "TPSQTP10SQ"))
    )
    (comp (ref "TP9")
      (value "TPSQTP10SQ")
      (footprint "eagle-import:TP10SQ")
      (libsource (lib "eagle-import") (part "TPSQTP10SQ"))
    )
    (comp (ref "U$1")
      (value "GTL2003")
      (footprint "eagle-import:TSSOP20")
      (libsource (lib "eagle-import") (part "GTL2003"))
    )
    (comp (ref "X1")
      (value "Molex 45558-0003")
      (footprint "eagle-import:MOLEX-45558-0003")
      (libsource (lib "eagle-import") (part "MOLEX-45558-0003"))
    )
    (comp (ref "X2")
      (value "ISP")
      (footprint "eagle-import:1X06_270")
      (libsource (lib "eagle-import") (part "PINHD-1X6/270"))
    )
    (comp (ref "X3")
      (value "Molex 22-04-1031")
      (footprint "eagle-import:MOLEX-22-04-1031")
      (libsource (lib "eagle-import") (part "MOLEX-22-04-1031"))
    )
    (comp (ref "X4")
      (value "Würth 65100516121 / TE 1734035-2")
      (footprint "eagle-import:32005-301")
      (libsource (lib "eagle-import") (part "MINI-USB-SCHIELD-32005-301"))
    )
  )
  (nets
    (net (code "2") (name "+1V8") (class "Default")
      (node (ref "C125") (pin "1") (pinfunction "1_1") (pintype "passive"))
      (node (ref "U$1") (pin "2") (pinfunction "SREF_2") (pintype "bidirectional"))
    )
    (net (code "3") (name "+3V3") (class "Default")
      (node (ref "C1") (pin "2") (pinfunction "2_2") (pintype "passive"))
      (node (ref "C106") (pin "2") (pinfunction "2_2") (pintype "passive"))
      (node (ref "C107") (pin "2") (pinfunction "2_2") (pintype "passive"))
      (node (ref "C11") (pin "2") (pinfunction "2_2") (pintype "passive"))
      (node (ref "C114") (pin "2") (pinfunction "2_2") (pintype "passive"))
      (node (ref "C115") (pin "2") (pinfunction "2_2") (pintype "passive"))
      (node (ref "C123") (pin "2") (pinfunction "2_2") (pintype "passive"))
      (node (ref "C124") (pin "2") (pinfunction "2_2") (pintype "passive"))
      (node (ref "C126") (pin "1") (pinfunction "1_1") (pintype "passive"))
      (node (ref "C13") (pin "+") (pinfunction "+_+") (pintype "passive"))
      (node (ref "C14") (pin "2") (pinfunction "2_2") (pintype "passive"))
      (node (ref "C141") (pin "2") (pinfunction "2_2") (pintype "passive"))
      (node (ref "C142") (pin "2") (pinfunction "2_2") (pintype "passive"))
      (node (ref "C15") (pin "2") (pinfunction "2_2") (pintype "passive"))
      (node (ref "C150") (pin "2") (pinfunction "2_2") (pintype "passive"))
      (node (ref "C151") (pin "2") (pinfunction "2_2") (pintype "passive"))
      (node (ref "C23") (pin "2") (pinfunction "2_2") (pintype "passive"))
      (node (ref "C24") (pin "2") (pinfunction "2_2") (pintype "passive"))
      (node (ref "C34") (pin "2") (pinfunction "2_2") (pintype "passive"))
      (node (ref "C35") (pin "2") (pinfunction "2_2") (pintype "passive"))
      (node (ref "C43") (pin "2") (pinfunction "2_2") (pintype "passive"))
      (node (ref "C44") (pin "2") (pinfunction "2_2") (pintype "passive"))
      (node (ref "C52") (pin "2") (pinfunction "2_2") (pintype "passive"))
      (node (ref "C53") (pin "2") (pinfunction "2_2") (pintype "passive"))
      (node (ref "C61") (pin "2") (pinfunction "2_2") (pintype "passive"))
      (node (ref "C62") (pin "2") (pinfunction "2_2") (pintype "passive"))
      (node (ref "C70") (pin "2") (pinfunction "2_2") (pintype "passive"))
      (node (ref "C71") (pin "2") (pinfunction "2_2") (pintype "passive"))
      (node (ref "C79") (pin "2") (pinfunction "2_2") (pintype "passive"))
      (node (ref "C80") (pin "2") (pinfunction "2_2") (pintype "passive"))
      (node (ref "C88") (pin "2") (pinfunction "2_2") (pintype "passive"))
      (node (ref "C89") (pin "2") (pinfunction "2_2") (pintype "passive"))
      (node (ref "C97") (pin "2") (pinfunction "2_2") (pintype "passive"))
      (node (ref "C98") (pin "2") (pinfunction "2_2") (pintype "passive"))
      (node (ref "IC1") (pin "18") (pinfunction "TRACK_18") (pintype "passive"))
      (node (ref "IC10") (pin "24") (pinfunction "OVDD1_24") (pintype "passive"))
      (node (ref "IC10") (pin "37") (pinfunction "OVDD0_37") (pintype "passive"))
      (node (ref "IC11") (pin "24") (pinfunction "OVDD1_24") (pintype "passive"))
      (node (ref "IC11") (pin "37") (pinfunction "OVDD0_37") (pintype "passive"))
      (node (ref "IC12") (pin "24") (pinfunction "OVDD1_24") (pintype "passive"))
      (node (ref "IC12") (pin "37") (pinfunction "OVDD0_37") (pintype "passive"))
      (node (ref "IC13") (pin "24") (pinfunction "OVDD1_24") (pintype "passive"))
      (node (ref "IC13") (pin "37") (pinfunction "OVDD0_37") (pintype "passive"))
      (node (ref "IC14") (pin "24") (pinfunction "OVDD1_24") (pintype "passive"))
      (node (ref "IC14") (pin "37") (pinfunction "OVDD0_37") (pintype "passive"))
      (node (ref "IC15") (pin "24") (pinfunction "OVDD1_24") (pintype "passive"))
      (node (ref "IC15") (pin "37") (pinfunction "OVDD0_37") (pintype "passive"))
      (node (ref "IC16") (pin "24") (pinfunction "OVDD1_24") (pintype "passive"))
      (node (ref "IC16") (pin "37") (pinfunction "OVDD0_37") (pintype "passive"))
      (node (ref "IC17") (pin "24") (pinfunction "OVDD1_24") (pintype "passive"))
      (node (ref "IC17") (pin "37") (pinfunction "OVDD0_37") (pintype "passive"))
      (node (ref "IC19") (pin "24") (pinfunction "OVDD1_24") (pintype "passive"))
      (node (ref "IC19") (pin "37") (pinfunction "OVDD0_37") (pintype "passive"))
      (node (ref "IC2") (pin "1") (pinfunction "VCC_1") (pintype "passive"))
      (node (ref "IC2") (pin "8") (pinfunction "OE_8") (pintype "passive"))
      (node (ref "IC20") (pin "24") (pinfunction "OVDD1_24") (pintype "passive"))
      (node (ref "IC20") (pin "37") (pinfunction "OVDD0_37") (pintype "passive"))
      (node (ref "IC3") (pin "4") (pinfunction "FB_4") (pintype "input"))
      (node (ref "IC4") (pin "1") (pinfunction "VCC_1") (pintype "passive"))
      (node (ref "IC5") (pin "14") (pinfunction "VCC_14") (pintype "power_in"))
      (node (ref "IC6") (pin "24") (pinfunction "OVDD1_24") (pintype "passive"))
      (node (ref "IC6") (pin "37") (pinfunction "OVDD0_37") (pintype "passive"))
      (node (ref "IC7") (pin "24") (pinfunction "OVDD1_24") (pintype "passive"))
      (node (ref "IC7") (pin "37") (pinfunction "OVDD0_37") (pintype "passive"))
      (node (ref "IC8") (pin "24") (pinfunction "OVDD1_24") (pintype "passive"))
      (node (ref "IC8") (pin "37") (pinfunction "OVDD0_37") (pintype "passive"))
      (node (ref "IC9") (pin "24") (pinfunction "OVDD1_24") (pintype "passive"))
      (node (ref "IC9") (pin "37") (pinfunction "OVDD0_37") (pintype "passive"))
      (node (ref "L1") (pin "2") (pinfunction "2_2") (pintype "passive"))
      (node (ref "Q1") (pin "4") (pinfunction "VCC_4") (pintype "power_in"))
      (node (ref "R10") (pin "1") (pinfunction "1_1") (pintype "passive"))
      (node (ref "R11") (pin "1") (pinfunction "1_1") (pintype "passive"))
      (node (ref "R15") (pin "1") (pinfunction "1_1") (pintype "passive"))
      (node (ref "R16") (pin "1") (pinfunction "1_1") (pintype "passive"))
      (node (ref "R17") (pin "1") (pinfunction "1_1") (pintype "passive"))
      (node (ref "R18") (pin "1") (pinfunction "1_1") (pintype "passive"))
      (node (ref "R19") (pin "1") (pinfunction "1_1") (pintype "passive"))
      (node (ref "R20") (pin "1") (pinfunction "1_1") (pintype "passive"))
      (node (ref "R21") (pin "1") (pinfunction "1_1") (pintype "passive"))
      (node (ref "R22") (pin "1") (pinfunction "1_1") (pintype "passive"))
      (node (ref "R23") (pin "1") (pinfunction "1_1") (pintype "passive"))
      (node (ref "R24") (pin "1") (pinfunction "1_1") (pintype "passive"))
      (node (ref "R25") (pin "1") (pinfunction "1_1") (pintype "passive"))
      (node (ref "R26") (pin "1") (pinfunction "1_1") (pintype "passive"))
      (node (ref "R28") (pin "1") (pinfunction "1_1") (pintype "passive"))
      (node (ref "R29") (pin "1") (pinfunction "1_1") (pintype "passive"))
      (node (ref "R4") (pin "1") (pinfunction "1_1") (pintype "passive"))
      (node (ref "R5") (pin "1") (pinfunction "1_1") (pintype "passive"))
      (node (ref "R6") (pin "1") (pinfunction "1_1") (pintype "passive"))
      (node (ref "RT1") (pin "2") (pinfunction "2_2") (pintype "passive"))
      (node (ref "TP6") (pin "TP") (pinfunction "TP_TP") (pintype "input"))
      (node (ref "U$1") (pin "19") (pinfunction "DREF_19") (pintype "bidirectional"))
      (node (ref "U$1") (pin "20") (pinfunction "GREF_20") (pintype "bidirectional"))
      (node (ref "X2") (pin "2") (pinfunction "2_2") (pintype "passive"))
    )
    (net (code "4") (name "+12V") (class "Default")
      (node (ref "C2") (pin "+") (pinfunction "+_+") (pintype "passive"))
      (node (ref "C3") (pin "1") (pinfunction "1_1") (pintype "passive"))
      (node (ref "C4") (pin "1") (pinfunction "1_1") (pintype "passive"))
      (node (ref "C5") (pin "1") (pinfunction "1_1") (pintype "passive"))
      (node (ref "D2") (pin "C") (pinfunction "C_C") (pintype "passive"))
      (node (ref "IC1") (pin "2") (pinfunction "VI_2") (pintype "passive"))
      (node (ref "IC1") (pin "4") (pinfunction "VI_4") (pintype "passive"))
      (node (ref "IC1") (pin "6") (pinfunction "VI_6") (pintype "passive"))
      (node (ref "IC3") (pin "1") (pinfunction "IN_1") (pintype "input"))
      (node (ref "X1") (pin "1") (pinfunction "12V_1") (pintype "passive"))
      (node (ref "X1") (pin "2") (pinfunction "12V_2") (pintype "passive"))
      (node (ref "X1") (pin "3") (pinfunction "12V_3") (pintype "passive"))
      (node (ref "X3") (pin "2") (pinfunction "+12V_2") (pintype "passive"))
    )
    (net (code "6") (name "/~{MCLR}") (class "Default")
      (node (ref "IC4") (pin "4") (pinfunction "RA3/~{MCLR}_4") (pintype "passive"))
      (node (ref "R7") (pin "1") (pinfunction "1_1") (pintype "passive"))
      (node (ref "X2") (pin "1") (pinfunction "1_1") (pintype "passive"))
    )
    (net (code "7") (name "CLK1") (class "Default")
      (node (ref "IC10") (pin "9") (pinfunction "XCLKIN_9") (pintype "passive"))
      (node (ref "IC19") (pin "9") (pinfunction "XCLKIN_9") (pintype "passive"))
      (node (ref "IC2") (pin "2") (pinfunction "OUT1_2") (pintype "passive"))
      (node (ref "IC20") (pin "9") (pinfunction "XCLKIN_9") (pintype "passive"))
      (node (ref "IC6") (pin "9") (pinfunction "XCLKIN_9") (pintype "passive"))
      (node (ref "IC7") (pin "9") (pinfunction "XCLKIN_9") (pintype "passive"))
      (node (ref "IC8") (pin "9") (pinfunction "XCLKIN_9") (pintype "passive"))
      (node (ref "IC9") (pin "9") (pinfunction "XCLKIN_9") (pintype "passive"))
    )
    (net (code "8") (name "CLK2") (class "Default")
      (node (ref "IC11") (pin "9") (pinfunction "XCLKIN_9") (pintype "passive"))
      (node (ref "IC12") (pin "9") (pinfunction "XCLKIN_9") (pintype "passive"))
      (node (ref "IC13") (pin "9") (pinfunction "XCLKIN_9") (pintype "passive"))
      (node (ref "IC14") (pin "9") (pinfunction "XCLKIN_9") (pintype "passive"))
      (node (ref "IC15") (pin "9") (pinfunction "XCLKIN_9") (pintype "passive"))
      (node (ref "IC16") (pin "9") (pinfunction "XCLKIN_9") (pintype "passive"))
      (node (ref "IC17") (pin "9") (pinfunction "XCLKIN_9") (pintype "passive"))
      (node (ref "IC2") (pin "3") (pinfunction "OUT2_3") (pintype "passive"))
    )
    (net (code "9") (name "CONFIG1_1V8_N") (class "Default")
      (node (ref "IC6") (pin "2") (pinfunction "CONFIG_NI_2") (pintype "passive"))
      (node (ref "U$1") (pin "4") (pinfunction "S2_4") (pintype "bidirectional"))
    )
    (net (code "10") (name "CONFIG1_1V8_P") (class "Default")
      (node (ref "IC6") (pin "1") (pinfunction "CONFIG_PI_1") (pintype "passive"))
      (node (ref "U$1") (pin "3") (pinfunction "S1_3") (pintype "bidirectional"))
    )
    (net (code "11") (name "CONFIG1_N") (class "Default")
      (node (ref "IC4") (pin "8") (pinfunction "RC6_8") (pintype "passive"))
      (node (ref "U$1") (pin "17") (pinfunction "D2_17") (pintype "bidirectional"))
    )
    (net (code "12") (name "CONFIG1_P") (class "Default")
      (node (ref "IC4") (pin "9") (pinfunction "RC7_9") (pintype "passive"))
      (node (ref "U$1") (pin "18") (pinfunction "D1_18") (pintype "bidirectional"))
    )
    (net (code "13") (name "CONFIG2_1V8_N") (class "Default")
      (node (ref "IC11") (pin "2") (pinfunction "CONFIG_NI_2") (pintype "passive"))
      (node (ref "U$1") (pin "6") (pinfunction "S4_6") (pintype "bidirectional"))
    )
    (net (code "14") (name "CONFIG2_1V8_P") (class "Default")
      (node (ref "IC11") (pin "1") (pinfunction "CONFIG_PI_1") (pintype "passive"))
      (node (ref "U$1") (pin "5") (pinfunction "S3_5") (pintype "bidirectional"))
    )
    (net (code "15") (name "CONFIG2_N") (class "Default")
      (node (ref "IC4") (pin "7") (pinfunction "RC3_7") (pintype "passive"))
      (node (ref "U$1") (pin "15") (pinfunction "D4_15") (pintype "bidirectional"))
    )
    (net (code "16") (name "CONFIG2_P") (class "Default")
      (node (ref "IC4") (pin "6") (pinfunction "RC4_6") (pintype "passive"))
      (node (ref "U$1") (pin "16") (pinfunction "D3_16") (pintype "bidirectional"))
    )
    (net (code "17") (name "DVDD") (class "Default")
      (node (ref "C10") (pin "+") (pinfunction "+_+") (pintype "passive"))
      (node (ref "C101") (pin "2") (pinfunction "2_2") (pintype "passive"))
      (node (ref "C102") (pin "2") (pinfunction "2_2") (pintype "passive"))
      (node (ref "C103") (pin "2") (pinfunction "2_2") (pintype "passive"))
      (node (ref "C104") (pin "2") (pinfunction "2_2") (pintype "passive"))
      (node (ref "C105") (pin "2") (pinfunction "2_2") (pintype "passive"))
      (node (ref "C109") (pin "2") (pinfunction "2_2") (pintype "passive"))
      (node (ref "C110") (pin "2") (pinfunction "2_2") (pintype "passive"))
      (node (ref "C111") (pin "2") (pinfunction "2_2") (pintype "passive"))
      (node (ref "C112") (pin "2") (pinfunction "2_2") (pintype "passive"))
      (node (ref "C113") (pin "2") (pinfunction "2_2") (pintype "passive"))
      (node (ref "C118") (pin "2") (pinfunction "2_2") (pintype "passive"))
      (node (ref "C119") (pin "2") (pinfunction "2_2") (pintype "passive"))
      (node (ref "C120") (pin "2") (pinfunction "2_2") (pintype "passive"))
      (node (ref "C121") (pin "2") (pinfunction "2_2") (pintype "passive"))
      (node (ref "C122") (pin "2") (pinfunction "2_2") (pintype "passive"))
      (node (ref "C136") (pin "2") (pinfunction "2_2") (pintype "passive"))
      (node (ref "C137") (pin "2") (pinfunction "2_2") (pintype "passive"))
      (node (ref "C138") (pin "2") (pinfunction "2_2") (pintype "passive"))
      (node (ref "C139") (pin "2") (pinfunction "2_2") (pintype "passive"))
      (node (ref "C140") (pin "2") (pinfunction "2_2") (pintype "passive"))
      (node (ref "C145") (pin "2") (pinfunction "2_2") (pintype "passive"))
      (node (ref "C146") (pin "2") (pinfunction "2_2") (pintype "passive"))
      (node (ref "C147") (pin "2") (pinfunction "2_2") (pintype "passive"))
      (node (ref "C148") (pin "2") (pinfunction "2_2") (pintype "passive"))
      (node (ref "C149") (pin "2") (pinfunction "2_2") (pintype "passive"))
      (node (ref "C18") (pin "2") (pinfunction "2_2") (pintype "passive"))
      (node (ref "C19") (pin "2") (pinfunction "2_2") (pintype "passive"))
      (node (ref "C20") (pin "2") (pinfunction "2_2") (pintype "passive"))
      (node (ref "C21") (pin "2") (pinfunction "2_2") (pintype "passive"))
      (node (ref "C22") (pin "2") (pinfunction "2_2") (pintype "passive"))
      (node (ref "C29") (pin "2") (pinfunction "2_2") (pintype "passive"))
      (node (ref "C30") (pin "2") (pinfunction "2_2") (pintype "passive"))
      (node (ref "C31") (pin "2") (pinfunction "2_2") (pintype "passive"))
      (node (ref "C32") (pin "2") (pinfunction "2_2") (pintype "passive"))
      (node (ref "C33") (pin "2") (pinfunction "2_2") (pintype "passive"))
      (node (ref "C38") (pin "2") (pinfunction "2_2") (pintype "passive"))
      (node (ref "C39") (pin "2") (pinfunction "2_2") (pintype "passive"))
      (node (ref "C40") (pin "2") (pinfunction "2_2") (pintype "passive"))
      (node (ref "C41") (pin "2") (pinfunction "2_2") (pintype "passive"))
      (node (ref "C42") (pin "2") (pinfunction "2_2") (pintype "passive"))
      (node (ref "C47") (pin "2") (pinfunction "2_2") (pintype "passive"))
      (node (ref "C48") (pin "2") (pinfunction "2_2") (pintype "passive"))
      (node (ref "C49") (pin "2") (pinfunction "2_2") (pintype "passive"))
      (node (ref "C50") (pin "2") (pinfunction "2_2") (pintype "passive"))
      (node (ref "C51") (pin "2") (pinfunction "2_2") (pintype "passive"))
      (node (ref "C56") (pin "2") (pinfunction "2_2") (pintype "passive"))
      (node (ref "C57") (pin "2") (pinfunction "2_2") (pintype "passive"))
      (node (ref "C58") (pin "2") (pinfunction "2_2") (pintype "passive"))
      (node (ref "C59") (pin "2") (pinfunction "2_2") (pintype "passive"))
      (node (ref "C6") (pin "1") (pinfunction "1_1") (pintype "passive"))
      (node (ref "C60") (pin "2") (pinfunction "2_2") (pintype "passive"))
      (node (ref "C65") (pin "2") (pinfunction "2_2") (pintype "passive"))
      (node (ref "C66") (pin "2") (pinfunction "2_2") (pintype "passive"))
      (node (ref "C67") (pin "2") (pinfunction "2_2") (pintype "passive"))
      (node (ref "C68") (pin "2") (pinfunction "2_2") (pintype "passive"))
      (node (ref "C69") (pin "2") (pinfunction "2_2") (pintype "passive"))
      (node (ref "C7") (pin "1") (pinfunction "1_1") (pintype "passive"))
      (node (ref "C74") (pin "2") (pinfunction "2_2") (pintype "passive"))
      (node (ref "C75") (pin "2") (pinfunction "2_2") (pintype "passive"))
      (node (ref "C76") (pin "2") (pinfunction "2_2") (pintype "passive"))
      (node (ref "C77") (pin "2") (pinfunction "2_2") (pintype "passive"))
      (node (ref "C78") (pin "2") (pinfunction "2_2") (pintype "passive"))
      (node (ref "C8") (pin "1") (pinfunction "1_1") (pintype "passive"))
      (node (ref "C83") (pin "2") (pinfunction "2_2") (pintype "passive"))
      (node (ref "C84") (pin "2") (pinfunction "2_2") (pintype "passive"))
      (node (ref "C85") (pin "2") (pinfunction "2_2") (pintype "passive"))
      (node (ref "C86") (pin "2") (pinfunction "2_2") (pintype "passive"))
      (node (ref "C87") (pin "2") (pinfunction "2_2") (pintype "passive"))
      (node (ref "C9") (pin "+") (pinfunction "+_+") (pintype "passive"))
      (node (ref "C92") (pin "2") (pinfunction "2_2") (pintype "passive"))
      (node (ref "C93") (pin "2") (pinfunction "2_2") (pintype "passive"))
      (node (ref "C94") (pin "2") (pinfunction "2_2") (pintype "passive"))
      (node (ref "C95") (pin "2") (pinfunction "2_2") (pintype "passive"))
      (node (ref "C96") (pin "2") (pinfunction "2_2") (pintype "passive"))
      (node (ref "IC1") (pin "12") (pinfunction "VO_12") (pintype "passive"))
      (node (ref "IC1") (pin "15") (pinfunction "VO_15") (pintype "passive"))
      (node (ref "IC1") (pin "9") (pinfunction "VO_9") (pintype "passive"))
      (node (ref "IC10") (pin "10") (pinfunction "DVDD_10") (pintype "passive"))
      (node (ref "IC10") (pin "11") (pinfunction "DVDD_11") (pintype "passive"))
      (node (ref "IC10") (pin "13") (pinfunction "DVDD_13") (pintype "passive"))
      (node (ref "IC10") (pin "14") (pinfunction "DVDD_14") (pintype "passive"))
      (node (ref "IC10") (pin "15") (pinfunction "DVDD_15") (pintype "passive"))
      (node (ref "IC10") (pin "18") (pinfunction "DVDD_18") (pintype "passive"))
      (node (ref "IC10") (pin "19") (pinfunction "DVDD_19") (pintype "passive"))
      (node (ref "IC10") (pin "20") (pinfunction "DVDD_20") (pintype "passive"))
      (node (ref "IC10") (pin "21") (pinfunction "DVDD_21") (pintype "passive"))
      (node (ref "IC10") (pin "22") (pinfunction "DVDD_22") (pintype "passive"))
      (node (ref "IC10") (pin "25") (pinfunction "DVDD_25") (pintype "passive"))
      (node (ref "IC10") (pin "26") (pinfunction "DVDD_26") (pintype "passive"))
      (node (ref "IC10") (pin "28") (pinfunction "DVDD_28") (pintype "passive"))
      (node (ref "IC10") (pin "29") (pinfunction "DVDD_29") (pintype "passive"))
      (node (ref "IC10") (pin "3") (pinfunction "DVDD_3") (pintype "passive"))
      (node (ref "IC10") (pin "30") (pinfunction "DVDD_30") (pintype "passive"))
      (node (ref "IC10") (pin "31") (pinfunction "DVDD_31") (pintype "passive"))
      (node (ref "IC10") (pin "32") (pinfunction "DVDD_32") (pintype "passive"))
      (node (ref "IC10") (pin "33") (pinfunction "DVDD_33") (pintype "passive"))
      (node (ref "IC10") (pin "34") (pinfunction "DVDD_34") (pintype "passive"))
      (node (ref "IC10") (pin "39") (pinfunction "DVDD_39") (pintype "passive"))
      (node (ref "IC10") (pin "4") (pinfunction "DVDD_4") (pintype "passive"))
      (node (ref "IC10") (pin "40") (pinfunction "DVDD_40") (pintype "passive"))
      (node (ref "IC10") (pin "41") (pinfunction "DVDD_41") (pintype "passive"))
      (node (ref "IC10") (pin "42") (pinfunction "DVDD_42") (pintype "passive"))
      (node (ref "IC10") (pin "45") (pinfunction "DVDD_45") (pintype "passive"))
      (node (ref "IC10") (pin "46") (pinfunction "DVDD_46") (pintype "passive"))
      (node (ref "IC10") (pin "47") (pinfunction "DVDD_47") (pintype "passive"))
      (node (ref "IC10") (pin "48") (pinfunction "DVDD_48") (pintype "passive"))
      (node (ref "IC11") (pin "10") (pinfunction "DVDD_10") (pintype "passive"))
      (node (ref "IC11") (pin "11") (pinfunction "DVDD_11") (pintype "passive"))
      (node (ref "IC11") (pin "13") (pinfunction "DVDD_13") (pintype "passive"))
      (node (ref "IC11") (pin "14") (pinfunction "DVDD_14") (pintype "passive"))
      (node (ref "IC11") (pin "15") (pinfunction "DVDD_15") (pintype "passive"))
      (node (ref "IC11") (pin "18") (pinfunction "DVDD_18") (pintype "passive"))
      (node (ref "IC11") (pin "19") (pinfunction "DVDD_19") (pintype "passive"))
      (node (ref "IC11") (pin "20") (pinfunction "DVDD_20") (pintype "passive"))
      (node (ref "IC11") (pin "21") (pinfunction "DVDD_21") (pintype "passive"))
      (node (ref "IC11") (pin "22") (pinfunction "DVDD_22") (pintype "passive"))
      (node (ref "IC11") (pin "25") (pinfunction "DVDD_25") (pintype "passive"))
      (node (ref "IC11") (pin "26") (pinfunction "DVDD_26") (pintype "passive"))
      (node (ref "IC11") (pin "28") (pinfunction "DVDD_28") (pintype "passive"))
      (node (ref "IC11") (pin "29") (pinfunction "DVDD_29") (pintype "passive"))
      (node (ref "IC11") (pin "3") (pinfunction "DVDD_3") (pintype "passive"))
      (node (ref "IC11") (pin "30") (pinfunction "DVDD_30") (pintype "passive"))
      (node (ref "IC11") (pin "31") (pinfunction "DVDD_31") (pintype "passive"))
      (node (ref "IC11") (pin "32") (pinfunction "DVDD_32") (pintype "passive"))
      (node (ref "IC11") (pin "33") (pinfunction "DVDD_33") (pintype "passive"))
      (node (ref "IC11") (pin "34") (pinfunction "DVDD_34") (pintype "passive"))
      (node (ref "IC11") (pin "39") (pinfunction "DVDD_39") (pintype "passive"))
      (node (ref "IC11") (pin "4") (pinfunction "DVDD_4") (pintype "passive"))
      (node (ref "IC11") (pin "40") (pinfunction "DVDD_40") (pintype "passive"))
      (node (ref "IC11") (pin "41") (pinfunction "DVDD_41") (pintype "passive"))
      (node (ref "IC11") (pin "42") (pinfunction "DVDD_42") (pintype "passive"))
      (node (ref "IC11") (pin "45") (pinfunction "DVDD_45") (pintype "passive"))
      (node (ref "IC11") (pin "46") (pinfunction "DVDD_46") (pintype "passive"))
      (node (ref "IC11") (pin "47") (pinfunction "DVDD_47") (pintype "passive"))
      (node (ref "IC11") (pin "48") (pinfunction "DVDD_48") (pintype "passive"))
      (node (ref "IC12") (pin "10") (pinfunction "DVDD_10") (pintype "passive"))
      (node (ref "IC12") (pin "11") (pinfunction "DVDD_11") (pintype "passive"))
      (node (ref "IC12") (pin "13") (pinfunction "DVDD_13") (pintype "passive"))
      (node (ref "IC12") (pin "14") (pinfunction "DVDD_14") (pintype "passive"))
      (node (ref "IC12") (pin "15") (pinfunction "DVDD_15") (pintype "passive"))
      (node (ref "IC12") (pin "18") (pinfunction "DVDD_18") (pintype "passive"))
      (node (ref "IC12") (pin "19") (pinfunction "DVDD_19") (pintype "passive"))
      (node (ref "IC12") (pin "20") (pinfunction "DVDD_20") (pintype "passive"))
      (node (ref "IC12") (pin "21") (pinfunction "DVDD_21") (pintype "passive"))
      (node (ref "IC12") (pin "22") (pinfunction "DVDD_22") (pintype "passive"))
      (node (ref "IC12") (pin "25") (pinfunction "DVDD_25") (pintype "passive"))
      (node (ref "IC12") (pin "26") (pinfunction "DVDD_26") (pintype "passive"))
      (node (ref "IC12") (pin "28") (pinfunction "DVDD_28") (pintype "passive"))
      (node (ref "IC12") (pin "29") (pinfunction "DVDD_29") (pintype "passive"))
      (node (ref "IC12") (pin "3") (pinfunction "DVDD_3") (pintype "passive"))
      (node (ref "IC12") (pin "30") (pinfunction "DVDD_30") (pintype "passive"))
      (node (ref "IC12") (pin "31") (pinfunction "DVDD_31") (pintype "passive"))
      (node (ref "IC12") (pin "32") (pinfunction "DVDD_32") (pintype "passive"))
      (node (ref "IC12") (pin "33") (pinfunction "DVDD_33") (pintype "passive"))
      (node (ref "IC12") (pin "34") (pinfunction "DVDD_34") (pintype "passive"))
      (node (ref "IC12") (pin "39") (pinfunction "DVDD_39") (pintype "passive"))
      (node (ref "IC12") (pin "4") (pinfunction "DVDD_4") (pintype "passive"))
      (node (ref "IC12") (pin "40") (pinfunction "DVDD_40") (pintype "passive"))
      (node (ref "IC12") (pin "41") (pinfunction "DVDD_41") (pintype "passive"))
      (node (ref "IC12") (pin "42") (pinfunction "DVDD_42") (pintype "passive"))
      (node (ref "IC12") (pin "45") (pinfunction "DVDD_45") (pintype "passive"))
      (node (ref "IC12") (pin "46") (pinfunction "DVDD_46") (pintype "passive"))
      (node (ref "IC12") (pin "47") (pinfunction "DVDD_47") (pintype "passive"))
      (node (ref "IC12") (pin "48") (pinfunction "DVDD_48") (pintype "passive"))
      (node (ref "IC13") (pin "10") (pinfunction "DVDD_10") (pintype "passive"))
      (node (ref "IC13") (pin "11") (pinfunction "DVDD_11") (pintype "passive"))
      (node (ref "IC13") (pin "13") (pinfunction "DVDD_13") (pintype "passive"))
      (node (ref "IC13") (pin "14") (pinfunction "DVDD_14") (pintype "passive"))
      (node (ref "IC13") (pin "15") (pinfunction "DVDD_15") (pintype "passive"))
      (node (ref "IC13") (pin "18") (pinfunction "DVDD_18") (pintype "passive"))
      (node (ref "IC13") (pin "19") (pinfunction "DVDD_19") (pintype "passive"))
      (node (ref "IC13") (pin "20") (pinfunction "DVDD_20") (pintype "passive"))
      (node (ref "IC13") (pin "21") (pinfunction "DVDD_21") (pintype "passive"))
      (node (ref "IC13") (pin "22") (pinfunction "DVDD_22") (pintype "passive"))
      (node (ref "IC13") (pin "25") (pinfunction "DVDD_25") (pintype "passive"))
      (node (ref "IC13") (pin "26") (pinfunction "DVDD_26") (pintype "passive"))
      (node (ref "IC13") (pin "28") (pinfunction "DVDD_28") (pintype "passive"))
      (node (ref "IC13") (pin "29") (pinfunction "DVDD_29") (pintype "passive"))
      (node (ref "IC13") (pin "3") (pinfunction "DVDD_3") (pintype "passive"))
      (node (ref "IC13") (pin "30") (pinfunction "DVDD_30") (pintype "passive"))
      (node (ref "IC13") (pin "31") (pinfunction "DVDD_31") (pintype "passive"))
      (node (ref "IC13") (pin "32") (pinfunction "DVDD_32") (pintype "passive"))
      (node (ref "IC13") (pin "33") (pinfunction "DVDD_33") (pintype "passive"))
      (node (ref "IC13") (pin "34") (pinfunction "DVDD_34") (pintype "passive"))
      (node (ref "IC13") (pin "39") (pinfunction "DVDD_39") (pintype "passive"))
      (node (ref "IC13") (pin "4") (pinfunction "DVDD_4") (pintype "passive"))
      (node (ref "IC13") (pin "40") (pinfunction "DVDD_40") (pintype "passive"))
      (node (ref "IC13") (pin "41") (pinfunction "DVDD_41") (pintype "passive"))
      (node (ref "IC13") (pin "42") (pinfunction "DVDD_42") (pintype "passive"))
      (node (ref "IC13") (pin "45") (pinfunction "DVDD_45") (pintype "passive"))
      (node (ref "IC13") (pin "46") (pinfunction "DVDD_46") (pintype "passive"))
      (node (ref "IC13") (pin "47") (pinfunction "DVDD_47") (pintype "passive"))
      (node (ref "IC13") (pin "48") (pinfunction "DVDD_48") (pintype "passive"))
      (node (ref "IC14") (pin "10") (pinfunction "DVDD_10") (pintype "passive"))
      (node (ref "IC14") (pin "11") (pinfunction "DVDD_11") (pintype "passive"))
      (node (ref "IC14") (pin "13") (pinfunction "DVDD_13") (pintype "passive"))
      (node (ref "IC14") (pin "14") (pinfunction "DVDD_14") (pintype "passive"))
      (node (ref "IC14") (pin "15") (pinfunction "DVDD_15") (pintype "passive"))
      (node (ref "IC14") (pin "18") (pinfunction "DVDD_18") (pintype "passive"))
      (node (ref "IC14") (pin "19") (pinfunction "DVDD_19") (pintype "passive"))
      (node (ref "IC14") (pin "20") (pinfunction "DVDD_20") (pintype "passive"))
      (node (ref "IC14") (pin "21") (pinfunction "DVDD_21") (pintype "passive"))
      (node (ref "IC14") (pin "22") (pinfunction "DVDD_22") (pintype "passive"))
      (node (ref "IC14") (pin "25") (pinfunction "DVDD_25") (pintype "passive"))
      (node (ref "IC14") (pin "26") (pinfunction "DVDD_26") (pintype "passive"))
      (node (ref "IC14") (pin "28") (pinfunction "DVDD_28") (pintype "passive"))
      (node (ref "IC14") (pin "29") (pinfunction "DVDD_29") (pintype "passive"))
      (node (ref "IC14") (pin "3") (pinfunction "DVDD_3") (pintype "passive"))
      (node (ref "IC14") (pin "30") (pinfunction "DVDD_30") (pintype "passive"))
      (node (ref "IC14") (pin "31") (pinfunction "DVDD_31") (pintype "passive"))
      (node (ref "IC14") (pin "32") (pinfunction "DVDD_32") (pintype "passive"))
      (node (ref "IC14") (pin "33") (pinfunction "DVDD_33") (pintype "passive"))
      (node (ref "IC14") (pin "34") (pinfunction "DVDD_34") (pintype "passive"))
      (node (ref "IC14") (pin "39") (pinfunction "DVDD_39") (pintype "passive"))
      (node (ref "IC14") (pin "4") (pinfunction "DVDD_4") (pintype "passive"))
      (node (ref "IC14") (pin "40") (pinfunction "DVDD_40") (pintype "passive"))
      (node (ref "IC14") (pin "41") (pinfunction "DVDD_41") (pintype "passive"))
      (node (ref "IC14") (pin "42") (pinfunction "DVDD_42") (pintype "passive"))
      (node (ref "IC14") (pin "45") (pinfunction "DVDD_45") (pintype "passive"))
      (node (ref "IC14") (pin "46") (pinfunction "DVDD_46") (pintype "passive"))
      (node (ref "IC14") (pin "47") (pinfunction "DVDD_47") (pintype "passive"))
      (node (ref "IC14") (pin "48") (pinfunction "DVDD_48") (pintype "passive"))
      (node (ref "IC15") (pin "10") (pinfunction "DVDD_10") (pintype "passive"))
      (node (ref "IC15") (pin "11") (pinfunction "DVDD_11") (pintype "passive"))
      (node (ref "IC15") (pin "13") (pinfunction "DVDD_13") (pintype "passive"))
      (node (ref "IC15") (pin "14") (pinfunction "DVDD_14") (pintype "passive"))
      (node (ref "IC15") (pin "15") (pinfunction "DVDD_15") (pintype "passive"))
      (node (ref "IC15") (pin "18") (pinfunction "DVDD_18") (pintype "passive"))
      (node (ref "IC15") (pin "19") (pinfunction "DVDD_19") (pintype "passive"))
      (node (ref "IC15") (pin "20") (pinfunction "DVDD_20") (pintype "passive"))
      (node (ref "IC15") (pin "21") (pinfunction "DVDD_21") (pintype "passive"))
      (node (ref "IC15") (pin "22") (pinfunction "DVDD_22") (pintype "passive"))
      (node (ref "IC15") (pin "25") (pinfunction "DVDD_25") (pintype "passive"))
      (node (ref "IC15") (pin "26") (pinfunction "DVDD_26") (pintype "passive"))
      (node (ref "IC15") (pin "28") (pinfunction "DVDD_28") (pintype "passive"))
      (node (ref "IC15") (pin "29") (pinfunction "DVDD_29") (pintype "passive"))
      (node (ref "IC15") (pin "3") (pinfunction "DVDD_3") (pintype "passive"))
      (node (ref "IC15") (pin "30") (pinfunction "DVDD_30") (pintype "passive"))
      (node (ref "IC15") (pin "31") (pinfunction "DVDD_31") (pintype "passive"))
      (node (ref "IC15") (pin "32") (pinfunction "DVDD_32") (pintype "passive"))
      (node (ref "IC15") (pin "33") (pinfunction "DVDD_33") (pintype "passive"))
      (node (ref "IC15") (pin "34") (pinfunction "DVDD_34") (pintype "passive"))
      (node (ref "IC15") (pin "39") (pinfunction "DVDD_39") (pintype "passive"))
      (node (ref "IC15") (pin "4") (pinfunction "DVDD_4") (pintype "passive"))
      (node (ref "IC15") (pin "40") (pinfunction "DVDD_40") (pintype "passive"))
      (node (ref "IC15") (pin "41") (pinfunction "DVDD_41") (pintype "passive"))
      (node (ref "IC15") (pin "42") (pinfunction "DVDD_42") (pintype "passive"))
      (node (ref "IC15") (pin "45") (pinfunction "DVDD_45") (pintype "passive"))
      (node (ref "IC15") (pin "46") (pinfunction "DVDD_46") (pintype "passive"))
      (node (ref "IC15") (pin "47") (pinfunction "DVDD_47") (pintype "passive"))
      (node (ref "IC15") (pin "48") (pinfunction "DVDD_48") (pintype "passive"))
      (node (ref "IC16") (pin "10") (pinfunction "DVDD_10") (pintype "passive"))
      (node (ref "IC16") (pin "11") (pinfunction "DVDD_11") (pintype "passive"))
      (node (ref "IC16") (pin "13") (pinfunction "DVDD_13") (pintype "passive"))
      (node (ref "IC16") (pin "14") (pinfunction "DVDD_14") (pintype "passive"))
      (node (ref "IC16") (pin "15") (pinfunction "DVDD_15") (pintype "passive"))
      (node (ref "IC16") (pin "18") (pinfunction "DVDD_18") (pintype "passive"))
      (node (ref "IC16") (pin "19") (pinfunction "DVDD_19") (pintype "passive"))
      (node (ref "IC16") (pin "20") (pinfunction "DVDD_20") (pintype "passive"))
      (node (ref "IC16") (pin "21") (pinfunction "DVDD_21") (pintype "passive"))
      (node (ref "IC16") (pin "22") (pinfunction "DVDD_22") (pintype "passive"))
      (node (ref "IC16") (pin "25") (pinfunction "DVDD_25") (pintype "passive"))
      (node (ref "IC16") (pin "26") (pinfunction "DVDD_26") (pintype "passive"))
      (node (ref "IC16") (pin "28") (pinfunction "DVDD_28") (pintype "passive"))
      (node (ref "IC16") (pin "29") (pinfunction "DVDD_29") (pintype "passive"))
      (node (ref "IC16") (pin "3") (pinfunction "DVDD_3") (pintype "passive"))
      (node (ref "IC16") (pin "30") (pinfunction "DVDD_30") (pintype "passive"))
      (node (ref "IC16") (pin "31") (pinfunction "DVDD_31") (pintype "passive"))
      (node (ref "IC16") (pin "32") (pinfunction "DVDD_32") (pintype "passive"))
      (node (ref "IC16") (pin "33") (pinfunction "DVDD_33") (pintype "passive"))
      (node (ref "IC16") (pin "34") (pinfunction "DVDD_34") (pintype "passive"))
      (node (ref "IC16") (pin "39") (pinfunction "DVDD_39") (pintype "passive"))
      (node (ref "IC16") (pin "4") (pinfunction "DVDD_4") (pintype "passive"))
      (node (ref "IC16") (pin "40") (pinfunction "DVDD_40") (pintype "passive"))
      (node (ref "IC16") (pin "41") (pinfunction "DVDD_41") (pintype "passive"))
      (node (ref "IC16") (pin "42") (pinfunction "DVDD_42") (pintype "passive"))
      (node (ref "IC16") (pin "45") (pinfunction "DVDD_45") (pintype "passive"))
      (node (ref "IC16") (pin "46") (pinfunction "DVDD_46") (pintype "passive"))
      (node (ref "IC16") (pin "47") (pinfunction "DVDD_47") (pintype "passive"))
      (node (ref "IC16") (pin "48") (pinfunction "DVDD_48") (pintype "passive"))
      (node (ref "IC17") (pin "10") (pinfunction "DVDD_10") (pintype "passive"))
      (node (ref "IC17") (pin "11") (pinfunction "DVDD_11") (pintype "passive"))
      (node (ref "IC17") (pin "13") (pinfunction "DVDD_13") (pintype "passive"))
      (node (ref "IC17") (pin "14") (pinfunction "DVDD_14") (pintype "passive"))
      (node (ref "IC17") (pin "15") (pinfunction "DVDD_15") (pintype "passive"))
      (node (ref "IC17") (pin "18") (pinfunction "DVDD_18") (pintype "passive"))
      (node (ref "IC17") (pin "19") (pinfunction "DVDD_19") (pintype "passive"))
      (node (ref "IC17") (pin "20") (pinfunction "DVDD_20") (pintype "passive"))
      (node (ref "IC17") (pin "21") (pinfunction "DVDD_21") (pintype "passive"))
      (node (ref "IC17") (pin "22") (pinfunction "DVDD_22") (pintype "passive"))
      (node (ref "IC17") (pin "25") (pinfunction "DVDD_25") (pintype "passive"))
      (node (ref "IC17") (pin "26") (pinfunction "DVDD_26") (pintype "passive"))
      (node (ref "IC17") (pin "28") (pinfunction "DVDD_28") (pintype "passive"))
      (node (ref "IC17") (pin "29") (pinfunction "DVDD_29") (pintype "passive"))
      (node (ref "IC17") (pin "3") (pinfunction "DVDD_3") (pintype "passive"))
      (node (ref "IC17") (pin "30") (pinfunction "DVDD_30") (pintype "passive"))
      (node (ref "IC17") (pin "31") (pinfunction "DVDD_31") (pintype "passive"))
      (node (ref "IC17") (pin "32") (pinfunction "DVDD_32") (pintype "passive"))
      (node (ref "IC17") (pin "33") (pinfunction "DVDD_33") (pintype "passive"))
      (node (ref "IC17") (pin "34") (pinfunction "DVDD_34") (pintype "passive"))
      (node (ref "IC17") (pin "39") (pinfunction "DVDD_39") (pintype "passive"))
      (node (ref "IC17") (pin "4") (pinfunction "DVDD_4") (pintype "passive"))
      (node (ref "IC17") (pin "40") (pinfunction "DVDD_40") (pintype "passive"))
      (node (ref "IC17") (pin "41") (pinfunction "DVDD_41") (pintype "passive"))
      (node (ref "IC17") (pin "42") (pinfunction "DVDD_42") (pintype "passive"))
      (node (ref "IC17") (pin "45") (pinfunction "DVDD_45") (pintype "passive"))
      (node (ref "IC17") (pin "46") (pinfunction "DVDD_46") (pintype "passive"))
      (node (ref "IC17") (pin "47") (pinfunction "DVDD_47") (pintype "passive"))
      (node (ref "IC17") (pin "48") (pinfunction "DVDD_48") (pintype "passive"))
      (node (ref "IC19") (pin "10") (pinfunction "DVDD_10") (pintype "passive"))
      (node (ref "IC19") (pin "11") (pinfunction "DVDD_11") (pintype "passive"))
      (node (ref "IC19") (pin "13") (pinfunction "DVDD_13") (pintype "passive"))
      (node (ref "IC19") (pin "14") (pinfunction "DVDD_14") (pintype "passive"))
      (node (ref "IC19") (pin "15") (pinfunction "DVDD_15") (pintype "passive"))
      (node (ref "IC19") (pin "18") (pinfunction "DVDD_18") (pintype "passive"))
      (node (ref "IC19") (pin "19") (pinfunction "DVDD_19") (pintype "passive"))
      (node (ref "IC19") (pin "20") (pinfunction "DVDD_20") (pintype "passive"))
      (node (ref "IC19") (pin "21") (pinfunction "DVDD_21") (pintype "passive"))
      (node (ref "IC19") (pin "22") (pinfunction "DVDD_22") (pintype "passive"))
      (node (ref "IC19") (pin "25") (pinfunction "DVDD_25") (pintype "passive"))
      (node (ref "IC19") (pin "26") (pinfunction "DVDD_26") (pintype "passive"))
      (node (ref "IC19") (pin "28") (pinfunction "DVDD_28") (pintype "passive"))
      (node (ref "IC19") (pin "29") (pinfunction "DVDD_29") (pintype "passive"))
      (node (ref "IC19") (pin "3") (pinfunction "DVDD_3") (pintype "passive"))
      (node (ref "IC19") (pin "30") (pinfunction "DVDD_30") (pintype "passive"))
      (node (ref "IC19") (pin "31") (pinfunction "DVDD_31") (pintype "passive"))
      (node (ref "IC19") (pin "32") (pinfunction "DVDD_32") (pintype "passive"))
      (node (ref "IC19") (pin "33") (pinfunction "DVDD_33") (pintype "passive"))
      (node (ref "IC19") (pin "34") (pinfunction "DVDD_34") (pintype "passive"))
      (node (ref "IC19") (pin "39") (pinfunction "DVDD_39") (pintype "passive"))
      (node (ref "IC19") (pin "4") (pinfunction "DVDD_4") (pintype "passive"))
      (node (ref "IC19") (pin "40") (pinfunction "DVDD_40") (pintype "passive"))
      (node (ref "IC19") (pin "41") (pinfunction "DVDD_41") (pintype "passive"))
      (node (ref "IC19") (pin "42") (pinfunction "DVDD_42") (pintype "passive"))
      (node (ref "IC19") (pin "45") (pinfunction "DVDD_45") (pintype "passive"))
      (node (ref "IC19") (pin "46") (pinfunction "DVDD_46") (pintype "passive"))
      (node (ref "IC19") (pin "47") (pinfunction "DVDD_47") (pintype "passive"))
      (node (ref "IC19") (pin "48") (pinfunction "DVDD_48") (pintype "passive"))
      (node (ref "IC20") (pin "10") (pinfunction "DVDD_10") (pintype "passive"))
      (node (ref "IC20") (pin "11") (pinfunction "DVDD_11") (pintype "passive"))
      (node (ref "IC20") (pin "13") (pinfunction "DVDD_13") (pintype "passive"))
      (node (ref "IC20") (pin "14") (pinfunction "DVDD_14") (pintype "passive"))
      (node (ref "IC20") (pin "15") (pinfunction "DVDD_15") (pintype "passive"))
      (node (ref "IC20") (pin "18") (pinfunction "DVDD_18") (pintype "passive"))
      (node (ref "IC20") (pin "19") (pinfunction "DVDD_19") (pintype "passive"))
      (node (ref "IC20") (pin "20") (pinfunction "DVDD_20") (pintype "passive"))
      (node (ref "IC20") (pin "21") (pinfunction "DVDD_21") (pintype "passive"))
      (node (ref "IC20") (pin "22") (pinfunction "DVDD_22") (pintype "passive"))
      (node (ref "IC20") (pin "25") (pinfunction "DVDD_25") (pintype "passive"))
      (node (ref "IC20") (pin "26") (pinfunction "DVDD_26") (pintype "passive"))
      (node (ref "IC20") (pin "28") (pinfunction "DVDD_28") (pintype "passive"))
      (node (ref "IC20") (pin "29") (pinfunction "DVDD_29") (pintype "passive"))
      (node (ref "IC20") (pin "3") (pinfunction "DVDD_3") (pintype "passive"))
      (node (ref "IC20") (pin "30") (pinfunction "DVDD_30") (pintype "passive"))
      (node (ref "IC20") (pin "31") (pinfunction "DVDD_31") (pintype "passive"))
      (node (ref "IC20") (pin "32") (pinfunction "DVDD_32") (pintype "passive"))
      (node (ref "IC20") (pin "33") (pinfunction "DVDD_33") (pintype "passive"))
      (node (ref "IC20") (pin "34") (pinfunction "DVDD_34") (pintype "passive"))
      (node (ref "IC20") (pin "39") (pinfunction "DVDD_39") (pintype "passive"))
      (node (ref "IC20") (pin "4") (pinfunction "DVDD_4") (pintype "passive"))
      (node (ref "IC20") (pin "40") (pinfunction "DVDD_40") (pintype "passive"))
      (node (ref "IC20") (pin "41") (pinfunction "DVDD_41") (pintype "passive"))
      (node (ref "IC20") (pin "42") (pinfunction "DVDD_42") (pintype "passive"))
      (node (ref "IC20") (pin "45") (pinfunction "DVDD_45") (pintype "passive"))
      (node (ref "IC20") (pin "46") (pinfunction "DVDD_46") (pintype "passive"))
      (node (ref "IC20") (pin "47") (pinfunction "DVDD_47") (pintype "passive"))
      (node (ref "IC20") (pin "48") (pinfunction "DVDD_48") (pintype "passive"))
      (node (ref "IC6") (pin "10") (pinfunction "DVDD_10") (pintype "passive"))
      (node (ref "IC6") (pin "11") (pinfunction "DVDD_11") (pintype "passive"))
      (node (ref "IC6") (pin "13") (pinfunction "DVDD_13") (pintype "passive"))
      (node (ref "IC6") (pin "14") (pinfunction "DVDD_14") (pintype "passive"))
      (node (ref "IC6") (pin "15") (pinfunction "DVDD_15") (pintype "passive"))
      (node (ref "IC6") (pin "18") (pinfunction "DVDD_18") (pintype "passive"))
      (node (ref "IC6") (pin "19") (pinfunction "DVDD_19") (pintype "passive"))
      (node (ref "IC6") (pin "20") (pinfunction "DVDD_20") (pintype "passive"))
      (node (ref "IC6") (pin "21") (pinfunction "DVDD_21") (pintype "passive"))
      (node (ref "IC6") (pin "22") (pinfunction "DVDD_22") (pintype "passive"))
      (node (ref "IC6") (pin "25") (pinfunction "DVDD_25") (pintype "passive"))
      (node (ref "IC6") (pin "26") (pinfunction "DVDD_26") (pintype "passive"))
      (node (ref "IC6") (pin "28") (pinfunction "DVDD_28") (pintype "passive"))
      (node (ref "IC6") (pin "29") (pinfunction "DVDD_29") (pintype "passive"))
      (node (ref "IC6") (pin "3") (pinfunction "DVDD_3") (pintype "passive"))
      (node (ref "IC6") (pin "30") (pinfunction "DVDD_30") (pintype "passive"))
      (node (ref "IC6") (pin "31") (pinfunction "DVDD_31") (pintype "passive"))
      (node (ref "IC6") (pin "32") (pinfunction "DVDD_32") (pintype "passive"))
      (node (ref "IC6") (pin "33") (pinfunction "DVDD_33") (pintype "passive"))
      (node (ref "IC6") (pin "34") (pinfunction "DVDD_34") (pintype "passive"))
      (node (ref "IC6") (pin "39") (pinfunction "DVDD_39") (pintype "passive"))
      (node (ref "IC6") (pin "4") (pinfunction "DVDD_4") (pintype "passive"))
      (node (ref "IC6") (pin "40") (pinfunction "DVDD_40") (pintype "passive"))
      (node (ref "IC6") (pin "41") (pinfunction "DVDD_41") (pintype "passive"))
      (node (ref "IC6") (pin "42") (pinfunction "DVDD_42") (pintype "passive"))
      (node (ref "IC6") (pin "45") (pinfunction "DVDD_45") (pintype "passive"))
      (node (ref "IC6") (pin "46") (pinfunction "DVDD_46") (pintype "passive"))
      (node (ref "IC6") (pin "47") (pinfunction "DVDD_47") (pintype "passive"))
      (node (ref "IC6") (pin "48") (pinfunction "DVDD_48") (pintype "passive"))
      (node (ref "IC7") (pin "10") (pinfunction "DVDD_10") (pintype "passive"))
      (node (ref "IC7") (pin "11") (pinfunction "DVDD_11") (pintype "passive"))
      (node (ref "IC7") (pin "13") (pinfunction "DVDD_13") (pintype "passive"))
      (node (ref "IC7") (pin "14") (pinfunction "DVDD_14") (pintype "passive"))
      (node (ref "IC7") (pin "15") (pinfunction "DVDD_15") (pintype "passive"))
      (node (ref "IC7") (pin "18") (pinfunction "DVDD_18") (pintype "passive"))
      (node (ref "IC7") (pin "19") (pinfunction "DVDD_19") (pintype "passive"))
      (node (ref "IC7") (pin "20") (pinfunction "DVDD_20") (pintype "passive"))
      (node (ref "IC7") (pin "21") (pinfunction "DVDD_21") (pintype "passive"))
      (node (ref "IC7") (pin "22") (pinfunction "DVDD_22") (pintype "passive"))
      (node (ref "IC7") (pin "25") (pinfunction "DVDD_25") (pintype "passive"))
      (node (ref "IC7") (pin "26") (pinfunction "DVDD_26") (pintype "passive"))
      (node (ref "IC7") (pin "28") (pinfunction "DVDD_28") (pintype "passive"))
      (node (ref "IC7") (pin "29") (pinfunction "DVDD_29") (pintype "passive"))
      (node (ref "IC7") (pin "3") (pinfunction "DVDD_3") (pintype "passive"))
      (node (ref "IC7") (pin "30") (pinfunction "DVDD_30") (pintype "passive"))
      (node (ref "IC7") (pin "31") (pinfunction "DVDD_31") (pintype "passive"))
      (node (ref "IC7") (pin "32") (pinfunction "DVDD_32") (pintype "passive"))
      (node (ref "IC7") (pin "33") (pinfunction "DVDD_33") (pintype "passive"))
      (node (ref "IC7") (pin "34") (pinfunction "DVDD_34") (pintype "passive"))
      (node (ref "IC7") (pin "39") (pinfunction "DVDD_39") (pintype "passive"))
      (node (ref "IC7") (pin "4") (pinfunction "DVDD_4") (pintype "passive"))
      (node (ref "IC7") (pin "40") (pinfunction "DVDD_40") (pintype "passive"))
      (node (ref "IC7") (pin "41") (pinfunction "DVDD_41") (pintype "passive"))
      (node (ref "IC7") (pin "42") (pinfunction "DVDD_42") (pintype "passive"))
      (node (ref "IC7") (pin "45") (pinfunction "DVDD_45") (pintype "passive"))
      (node (ref "IC7") (pin "46") (pinfunction "DVDD_46") (pintype "passive"))
      (node (ref "IC7") (pin "47") (pinfunction "DVDD_47") (pintype "passive"))
      (node (ref "IC7") (pin "48") (pinfunction "DVDD_48") (pintype "passive"))
      (node (ref "IC8") (pin "10") (pinfunction "DVDD_10") (pintype "passive"))
      (node (ref "IC8") (pin "11") (pinfunction "DVDD_11") (pintype "passive"))
      (node (ref "IC8") (pin "13") (pinfunction "DVDD_13") (pintype "passive"))
      (node (ref "IC8") (pin "14") (pinfunction "DVDD_14") (pintype "passive"))
      (node (ref "IC8") (pin "15") (pinfunction "DVDD_15") (pintype "passive"))
      (node (ref "IC8") (pin "18") (pinfunction "DVDD_18") (pintype "passive"))
      (node (ref "IC8") (pin "19") (pinfunction "DVDD_19") (pintype "passive"))
      (node (ref "IC8") (pin "20") (pinfunction "DVDD_20") (pintype "passive"))
      (node (ref "IC8") (pin "21") (pinfunction "DVDD_21") (pintype "passive"))
      (node (ref "IC8") (pin "22") (pinfunction "DVDD_22") (pintype "passive"))
      (node (ref "IC8") (pin "25") (pinfunction "DVDD_25") (pintype "passive"))
      (node (ref "IC8") (pin "26") (pinfunction "DVDD_26") (pintype "passive"))
      (node (ref "IC8") (pin "28") (pinfunction "DVDD_28") (pintype "passive"))
      (node (ref "IC8") (pin "29") (pinfunction "DVDD_29") (pintype "passive"))
      (node (ref "IC8") (pin "3") (pinfunction "DVDD_3") (pintype "passive"))
      (node (ref "IC8") (pin "30") (pinfunction "DVDD_30") (pintype "passive"))
      (node (ref "IC8") (pin "31") (pinfunction "DVDD_31") (pintype "passive"))
      (node (ref "IC8") (pin "32") (pinfunction "DVDD_32") (pintype "passive"))
      (node (ref "IC8") (pin "33") (pinfunction "DVDD_33") (pintype "passive"))
      (node (ref "IC8") (pin "34") (pinfunction "DVDD_34") (pintype "passive"))
      (node (ref "IC8") (pin "39") (pinfunction "DVDD_39") (pintype "passive"))
      (node (ref "IC8") (pin "4") (pinfunction "DVDD_4") (pintype "passive"))
      (node (ref "IC8") (pin "40") (pinfunction "DVDD_40") (pintype "passive"))
      (node (ref "IC8") (pin "41") (pinfunction "DVDD_41") (pintype "passive"))
      (node (ref "IC8") (pin "42") (pinfunction "DVDD_42") (pintype "passive"))
      (node (ref "IC8") (pin "45") (pinfunction "DVDD_45") (pintype "passive"))
      (node (ref "IC8") (pin "46") (pinfunction "DVDD_46") (pintype "passive"))
      (node (ref "IC8") (pin "47") (pinfunction "DVDD_47") (pintype "passive"))
      (node (ref "IC8") (pin "48") (pinfunction "DVDD_48") (pintype "passive"))
      (node (ref "IC9") (pin "10") (pinfunction "DVDD_10") (pintype "passive"))
      (node (ref "IC9") (pin "11") (pinfunction "DVDD_11") (pintype "passive"))
      (node (ref "IC9") (pin "13") (pinfunction "DVDD_13") (pintype "passive"))
      (node (ref "IC9") (pin "14") (pinfunction "DVDD_14") (pintype "passive"))
      (node (ref "IC9") (pin "15") (pinfunction "DVDD_15") (pintype "passive"))
      (node (ref "IC9") (pin "18") (pinfunction "DVDD_18") (pintype "passive"))
      (node (ref "IC9") (pin "19") (pinfunction "DVDD_19") (pintype "passive"))
      (node (ref "IC9") (pin "20") (pinfunction "DVDD_20") (pintype "passive"))
      (node (ref "IC9") (pin "21") (pinfunction "DVDD_21") (pintype "passive"))
      (node (ref "IC9") (pin "22") (pinfunction "DVDD_22") (pintype "passive"))
      (node (ref "IC9") (pin "25") (pinfunction "DVDD_25") (pintype "passive"))
      (node (ref "IC9") (pin "26") (pinfunction "DVDD_26") (pintype "passive"))
      (node (ref "IC9") (pin "28") (pinfunction "DVDD_28") (pintype "passive"))
      (node (ref "IC9") (pin "29") (pinfunction "DVDD_29") (pintype "passive"))
      (node (ref "IC9") (pin "3") (pinfunction "DVDD_3") (pintype "passive"))
      (node (ref "IC9") (pin "30") (pinfunction "DVDD_30") (pintype "passive"))
      (node (ref "IC9") (pin "31") (pinfunction "DVDD_31") (pintype "passive"))
      (node (ref "IC9") (pin "32") (pinfunction "DVDD_32") (pintype "passive"))
      (node (ref "IC9") (pin "33") (pinfunction "DVDD_33") (pintype "passive"))
      (node (ref "IC9") (pin "34") (pinfunction "DVDD_34") (pintype "passive"))
      (node (ref "IC9") (pin "39") (pinfunction "DVDD_39") (pintype "passive"))
      (node (ref "IC9") (pin "4") (pinfunction "DVDD_4") (pintype "passive"))
      (node (ref "IC9") (pin "40") (pinfunction "DVDD_40") (pintype "passive"))
      (node (ref "IC9") (pin "41") (pinfunction "DVDD_41") (pintype "passive"))
      (node (ref "IC9") (pin "42") (pinfunction "DVDD_42") (pintype "passive"))
      (node (ref "IC9") (pin "45") (pinfunction "DVDD_45") (pintype "passive"))
      (node (ref "IC9") (pin "46") (pinfunction "DVDD_46") (pintype "passive"))
      (node (ref "IC9") (pin "47") (pinfunction "DVDD_47") (pintype "passive"))
      (node (ref "IC9") (pin "48") (pinfunction "DVDD_48") (pintype "passive"))
      (node (ref "L10") (pin "1") (pinfunction "1_1") (pintype "passive"))
      (node (ref "L11") (pin "1") (pinfunction "1_1") (pintype "passive"))
      (node (ref "L12") (pin "1") (pinfunction "1_1") (pintype "passive"))
      (node (ref "L13") (pin "1") (pinfunction "1_1") (pintype "passive"))
      (node (ref "L15") (pin "1") (pinfunction "1_1") (pintype "passive"))
      (node (ref "L16") (pin "1") (pinfunction "1_1") (pintype "passive"))
      (node (ref "L2") (pin "1") (pinfunction "1_1") (pintype "passive"))
      (node (ref "L3") (pin "1") (pinfunction "1_1") (pintype "passive"))
      (node (ref "L4") (pin "1") (pinfunction "1_1") (pintype "passive"))
      (node (ref "L5") (pin "1") (pinfunction "1_1") (pintype "passive"))
      (node (ref "L6") (pin "1") (pinfunction "1_1") (pintype "passive"))
      (node (ref "L7") (pin "1") (pinfunction "1_1") (pintype "passive"))
      (node (ref "L8") (pin "1") (pinfunction "1_1") (pintype "passive"))
      (node (ref "L9") (pin "1") (pinfunction "1_1") (pintype "passive"))
      (node (ref "R1") (pin "2") (pinfunction "2_2") (pintype "passive"))
    )
    (net (code "18") (name "FAN_PWM") (class "Default")
      (node (ref "IC4") (pin "5") (pinfunction "RC5_5") (pintype "passive"))
      (node (ref "R12") (pin "1") (pinfunction "1_1") (pintype "passive"))
    )
    (net (code "19") (name "GND") (class "Default")
      (node (ref "C1") (pin "1") (pinfunction "1_1") (pintype "passive"))
      (node (ref "C10") (pin "-") (pinfunction "-_-") (pintype "passive"))
      (node (ref "C100") (pin "2") (pinfunction "2_2") (pintype "passive"))
      (node (ref "C101") (pin "1") (pinfunction "1_1") (pintype "passive"))
      (node (ref "C102") (pin "1") (pinfunction "1_1") (pintype "passive"))
      (node (ref "C103") (pin "1") (pinfunction "1_1") (pintype "passive"))
      (node (ref "C104") (pin "1") (pinfunction "1_1") (pintype "passive"))
      (node (ref "C105") (pin "1") (pinfunction "1_1") (pintype "passive"))
      (node (ref "C106") (pin "1") (pinfunction "1_1") (pintype "passive"))
      (node (ref "C107") (pin "1") (pinfunction "1_1") (pintype "passive"))
      (node (ref "C108") (pin "2") (pinfunction "2_2") (pintype "passive"))
      (node (ref "C109") (pin "1") (pinfunction "1_1") (pintype "passive"))
      (node (ref "C11") (pin "1") (pinfunction "1_1") (pintype "passive"))
      (node (ref "C110") (pin "1") (pinfunction "1_1") (pintype "passive"))
      (node (ref "C111") (pin "1") (pinfunction "1_1") (pintype "passive"))
      (node (ref "C112") (pin "1") (pinfunction "1_1") (pintype "passive"))
      (node (ref "C113") (pin "1") (pinfunction "1_1") (pintype "passive"))
      (node (ref "C114") (pin "1") (pinfunction "1_1") (pintype "passive"))
      (node (ref "C115") (pin "1") (pinfunction "1_1") (pintype "passive"))
      (node (ref "C116") (pin "1") (pinfunction "1_1") (pintype "passive"))
      (node (ref "C117") (pin "2") (pinfunction "2_2") (pintype "passive"))
      (node (ref "C118") (pin "1") (pinfunction "1_1") (pintype "passive"))
      (node (ref "C119") (pin "1") (pinfunction "1_1") (pintype "passive"))
      (node (ref "C12") (pin "1") (pinfunction "1_1") (pintype "passive"))
      (node (ref "C120") (pin "1") (pinfunction "1_1") (pintype "passive"))
      (node (ref "C121") (pin "1") (pinfunction "1_1") (pintype "passive"))
      (node (ref "C122") (pin "1") (pinfunction "1_1") (pintype "passive"))
      (node (ref "C123") (pin "1") (pinfunction "1_1") (pintype "passive"))
      (node (ref "C124") (pin "1") (pinfunction "1_1") (pintype "passive"))
      (node (ref "C125") (pin "2") (pinfunction "2_2") (pintype "passive"))
      (node (ref "C126") (pin "2") (pinfunction "2_2") (pintype "passive"))
      (node (ref "C13") (pin "-") (pinfunction "-_-") (pintype "passive"))
      (node (ref "C134") (pin "1") (pinfunction "1_1") (pintype "passive"))
      (node (ref "C135") (pin "2") (pinfunction "2_2") (pintype "passive"))
      (node (ref "C136") (pin "1") (pinfunction "1_1") (pintype "passive"))
      (node (ref "C137") (pin "1") (pinfunction "1_1") (pintype "passive"))
      (node (ref "C138") (pin "1") (pinfunction "1_1") (pintype "passive"))
      (node (ref "C139") (pin "1") (pinfunction "1_1") (pintype "passive"))
      (node (ref "C14") (pin "1") (pinfunction "1_1") (pintype "passive"))
      (node (ref "C140") (pin "1") (pinfunction "1_1") (pintype "passive"))
      (node (ref "C141") (pin "1") (pinfunction "1_1") (pintype "passive"))
      (node (ref "C142") (pin "1") (pinfunction "1_1") (pintype "passive"))
      (node (ref "C143") (pin "1") (pinfunction "1_1") (pintype "passive"))
      (node (ref "C144") (pin "2") (pinfunction "2_2") (pintype "passive"))
      (node (ref "C145") (pin "1") (pinfunction "1_1") (pintype "passive"))
      (node (ref "C146") (pin "1") (pinfunction "1_1") (pintype "passive"))
      (node (ref "C147") (pin "1") (pinfunction "1_1") (pintype "passive"))
      (node (ref "C148") (pin "1") (pinfunction "1_1") (pintype "passive"))
      (node (ref "C149") (pin "1") (pinfunction "1_1") (pintype "passive"))
      (node (ref "C15") (pin "1") (pinfunction "1_1") (pintype "passive"))
      (node (ref "C150") (pin "1") (pinfunction "1_1") (pintype "passive"))
      (node (ref "C151") (pin "1") (pinfunction "1_1") (pintype "passive"))
      (node (ref "C16") (pin "1") (pinfunction "1_1") (pintype "passive"))
      (node (ref "C17") (pin "1") (pinfunction "1_1") (pintype "passive"))
      (node (ref "C18") (pin "1") (pinfunction "1_1") (pintype "passive"))
      (node (ref "C19") (pin "1") (pinfunction "1_1") (pintype "passive"))
      (node (ref "C2") (pin "-") (pinfunction "-_-") (pintype "passive"))
      (node (ref "C20") (pin "1") (pinfunction "1_1") (pintype "passive"))
      (node (ref "C21") (pin "1") (pinfunction "1_1") (pintype "passive"))
      (node (ref "C22") (pin "1") (pinfunction "1_1") (pintype "passive"))
      (node (ref "C23") (pin "1") (pinfunction "1_1") (pintype "passive"))
      (node (ref "C24") (pin "1") (pinfunction "1_1") (pintype "passive"))
      (node (ref "C25") (pin "2") (pinfunction "2_2") (pintype "passive"))
      (node (ref "C26") (pin "1") (pinfunction "1_1") (pintype "passive"))
      (node (ref "C27") (pin "1") (pinfunction "1_1") (pintype "passive"))
      (node (ref "C28") (pin "2") (pinfunction "2_2") (pintype "passive"))
      (node (ref "C29") (pin "1") (pinfunction "1_1") (pintype "passive"))
      (node (ref "C3") (pin "2") (pinfunction "2_2") (pintype "passive"))
      (node (ref "C30") (pin "1") (pinfunction "1_1") (pintype "passive"))
      (node (ref "C31") (pin "1") (pinfunction "1_1") (pintype "passive"))
      (node (ref "C32") (pin "1") (pinfunction "1_1") (pintype "passive"))
      (node (ref "C33") (pin "1") (pinfunction "1_1") (pintype "passive"))
      (node (ref "C34") (pin "1") (pinfunction "1_1") (pintype "passive"))
      (node (ref "C35") (pin "1") (pinfunction "1_1") (pintype "passive"))
      (node (ref "C36") (pin "1") (pinfunction "1_1") (pintype "passive"))
      (node (ref "C37") (pin "2") (pinfunction "2_2") (pintype "passive"))
      (node (ref "C38") (pin "1") (pinfunction "1_1") (pintype "passive"))
      (node (ref "C39") (pin "1") (pinfunction "1_1") (pintype "passive"))
      (node (ref "C4") (pin "2") (pinfunction "2_2") (pintype "passive"))
      (node (ref "C40") (pin "1") (pinfunction "1_1") (pintype "passive"))
      (node (ref "C41") (pin "1") (pinfunction "1_1") (pintype "passive"))
      (node (ref "C42") (pin "1") (pinfunction "1_1") (pintype "passive"))
      (node (ref "C43") (pin "1") (pinfunction "1_1") (pintype "passive"))
      (node (ref "C44") (pin "1") (pinfunction "1_1") (pintype "passive"))
      (node (ref "C45") (pin "1") (pinfunction "1_1") (pintype "passive"))
      (node (ref "C46") (pin "2") (pinfunction "2_2") (pintype "passive"))
      (node (ref "C47") (pin "1") (pinfunction "1_1") (pintype "passive"))
      (node (ref "C48") (pin "1") (pinfunction "1_1") (pintype "passive"))
      (node (ref "C49") (pin "1") (pinfunction "1_1") (pintype "passive"))
      (node (ref "C5") (pin "2") (pinfunction "2_2") (pintype "passive"))
      (node (ref "C50") (pin "1") (pinfunction "1_1") (pintype "passive"))
      (node (ref "C51") (pin "1") (pinfunction "1_1") (pintype "passive"))
      (node (ref "C52") (pin "1") (pinfunction "1_1") (pintype "passive"))
      (node (ref "C53") (pin "1") (pinfunction "1_1") (pintype "passive"))
      (node (ref "C54") (pin "1") (pinfunction "1_1") (pintype "passive"))
      (node (ref "C55") (pin "2") (pinfunction "2_2") (pintype "passive"))
      (node (ref "C56") (pin "1") (pinfunction "1_1") (pintype "passive"))
      (node (ref "C57") (pin "1") (pinfunction "1_1") (pintype "passive"))
      (node (ref "C58") (pin "1") (pinfunction "1_1") (pintype "passive"))
      (node (ref "C59") (pin "1") (pinfunction "1_1") (pintype "passive"))
      (node (ref "C6") (pin "2") (pinfunction "2_2") (pintype "passive"))
      (node (ref "C60") (pin "1") (pinfunction "1_1") (pintype "passive"))
      (node (ref "C61") (pin "1") (pinfunction "1_1") (pintype "passive"))
      (node (ref "C62") (pin "1") (pinfunction "1_1") (pintype "passive"))
      (node (ref "C63") (pin "1") (pinfunction "1_1") (pintype "passive"))
      (node (ref "C64") (pin "2") (pinfunction "2_2") (pintype "passive"))
      (node (ref "C65") (pin "1") (pinfunction "1_1") (pintype "passive"))
      (node (ref "C66") (pin "1") (pinfunction "1_1") (pintype "passive"))
      (node (ref "C67") (pin "1") (pinfunction "1_1") (pintype "passive"))
      (node (ref "C68") (pin "1") (pinfunction "1_1") (pintype "passive"))
      (node (ref "C69") (pin "1") (pinfunction "1_1") (pintype "passive"))
      (node (ref "C7") (pin "2") (pinfunction "2_2") (pintype "passive"))
      (node (ref "C70") (pin "1") (pinfunction "1_1") (pintype "passive"))
      (node (ref "C71") (pin "1") (pinfunction "1_1") (pintype "passive"))
      (node (ref "C72") (pin "1") (pinfunction "1_1") (pintype "passive"))
      (node (ref "C73") (pin "2") (pinfunction "2_2") (pintype "passive"))
      (node (ref "C74") (pin "1") (pinfunction "1_1") (pintype "passive"))
      (node (ref "C75") (pin "1") (pinfunction "1_1") (pintype "passive"))
      (node (ref "C76") (pin "1") (pinfunction "1_1") (pintype "passive"))
      (node (ref "C77") (pin "1") (pinfunction "1_1") (pintype "passive"))
      (node (ref "C78") (pin "1") (pinfunction "1_1") (pintype "passive"))
      (node (ref "C79") (pin "1") (pinfunction "1_1") (pintype "passive"))
      (node (ref "C8") (pin "2") (pinfunction "2_2") (pintype "passive"))
      (node (ref "C80") (pin "1") (pinfunction "1_1") (pintype "passive"))
      (node (ref "C81") (pin "1") (pinfunction "1_1") (pintype "passive"))
      (node (ref "C82") (pin "2") (pinfunction "2_2") (pintype "passive"))
      (node (ref "C83") (pin "1") (pinfunction "1_1") (pintype "passive"))
      (node (ref "C84") (pin "1") (pinfunction "1_1") (pintype "passive"))
      (node (ref "C85") (pin "1") (pinfunction "1_1") (pintype "passive"))
      (node (ref "C86") (pin "1") (pinfunction "1_1") (pintype "passive"))
      (node (ref "C87") (pin "1") (pinfunction "1_1") (pintype "passive"))
      (node (ref "C88") (pin "1") (pinfunction "1_1") (pintype "passive"))
      (node (ref "C89") (pin "1") (pinfunction "1_1") (pintype "passive"))
      (node (ref "C9") (pin "-") (pinfunction "-_-") (pintype "passive"))
      (node (ref "C90") (pin "1") (pinfunction "1_1") (pintype "passive"))
      (node (ref "C91") (pin "2") (pinfunction "2_2") (pintype "passive"))
      (node (ref "C92") (pin "1") (pinfunction "1_1") (pintype "passive"))
      (node (ref "C93") (pin "1") (pinfunction "1_1") (pintype "passive"))
      (node (ref "C94") (pin "1") (pinfunction "1_1") (pintype "passive"))
      (node (ref "C95") (pin "1") (pinfunction "1_1") (pintype "passive"))
      (node (ref "C96") (pin "1") (pinfunction "1_1") (pintype "passive"))
      (node (ref "C97") (pin "1") (pinfunction "1_1") (pintype "passive"))
      (node (ref "C98") (pin "1") (pinfunction "1_1") (pintype "passive"))
      (node (ref "C99") (pin "1") (pinfunction "1_1") (pintype "passive"))
      (node (ref "D1") (pin "A") (pinfunction "A_A") (pintype "passive"))
      (node (ref "IC1") (pin "1") (pinfunction "GND_1") (pintype "passive"))
      (node (ref "IC1") (pin "10") (pinfunction "GND_10") (pintype "passive"))
      (node (ref "IC1") (pin "13") (pinfunction "GND_13") (pintype "passive"))
      (node (ref "IC1") (pin "14") (pinfunction "SENSE-_14") (pintype "passive"))
      (node (ref "IC1") (pin "16") (pinfunction "GND_16") (pintype "passive"))
      (node (ref "IC1") (pin "3") (pinfunction "GND_3") (pintype "passive"))
      (node (ref "IC1") (pin "5") (pinfunction "GND_5") (pintype "passive"))
      (node (ref "IC10") (pin "12") (pinfunction "DVSS_12") (pintype "passive"))
      (node (ref "IC10") (pin "23") (pinfunction "OVSS1_23") (pintype "passive"))
      (node (ref "IC10") (pin "27") (pinfunction "DVSS_27") (pintype "passive"))
      (node (ref "IC10") (pin "38") (pinfunction "OVSS0_38") (pintype "passive"))
      (node (ref "IC10") (pin "5") (pinfunction "VSSA_PLL_5") (pintype "passive"))
      (node (ref "IC10") (pin "8") (pinfunction "VSS_PLL_8") (pintype "passive"))
      (node (ref "IC10") (pin "EXP") (pinfunction "EX-PAD_EXP") (pintype "passive"))
      (node (ref "IC11") (pin "12") (pinfunction "DVSS_12") (pintype "passive"))
      (node (ref "IC11") (pin "23") (pinfunction "OVSS1_23") (pintype "passive"))
      (node (ref "IC11") (pin "27") (pinfunction "DVSS_27") (pintype "passive"))
      (node (ref "IC11") (pin "38") (pinfunction "OVSS0_38") (pintype "passive"))
      (node (ref "IC11") (pin "5") (pinfunction "VSSA_PLL_5") (pintype "passive"))
      (node (ref "IC11") (pin "8") (pinfunction "VSS_PLL_8") (pintype "passive"))
      (node (ref "IC11") (pin "EXP") (pinfunction "EX-PAD_EXP") (pintype "passive"))
      (node (ref "IC12") (pin "12") (pinfunction "DVSS_12") (pintype "passive"))
      (node (ref "IC12") (pin "23") (pinfunction "OVSS1_23") (pintype "passive"))
      (node (ref "IC12") (pin "27") (pinfunction "DVSS_27") (pintype "passive"))
      (node (ref "IC12") (pin "38") (pinfunction "OVSS0_38") (pintype "passive"))
      (node (ref "IC12") (pin "5") (pinfunction "VSSA_PLL_5") (pintype "passive"))
      (node (ref "IC12") (pin "8") (pinfunction "VSS_PLL_8") (pintype "passive"))
      (node (ref "IC12") (pin "EXP") (pinfunction "EX-PAD_EXP") (pintype "passive"))
      (node (ref "IC13") (pin "12") (pinfunction "DVSS_12") (pintype "passive"))
      (node (ref "IC13") (pin "23") (pinfunction "OVSS1_23") (pintype "passive"))
      (node (ref "IC13") (pin "27") (pinfunction "DVSS_27") (pintype "passive"))
      (node (ref "IC13") (pin "38") (pinfunction "OVSS0_38") (pintype "passive"))
      (node (ref "IC13") (pin "5") (pinfunction "VSSA_PLL_5") (pintype "passive"))
      (node (ref "IC13") (pin "8") (pinfunction "VSS_PLL_8") (pintype "passive"))
      (node (ref "IC13") (pin "EXP") (pinfunction "EX-PAD_EXP") (pintype "passive"))
      (node (ref "IC14") (pin "12") (pinfunction "DVSS_12") (pintype "passive"))
      (node (ref "IC14") (pin "23") (pinfunction "OVSS1_23") (pintype "passive"))
      (node (ref "IC14") (pin "27") (pinfunction "DVSS_27") (pintype "passive"))
      (node (ref "IC14") (pin "38") (pinfunction "OVSS0_38") (pintype "passive"))
      (node (ref "IC14") (pin "5") (pinfunction "VSSA_PLL_5") (pintype "passive"))
      (node (ref "IC14") (pin "8") (pinfunction "VSS_PLL_8") (pintype "passive"))
      (node (ref "IC14") (pin "EXP") (pinfunction "EX-PAD_EXP") (pintype "passive"))
      (node (ref "IC15") (pin "12") (pinfunction "DVSS_12") (pintype "passive"))
      (node (ref "IC15") (pin "23") (pinfunction "OVSS1_23") (pintype "passive"))
      (node (ref "IC15") (pin "27") (pinfunction "DVSS_27") (pintype "passive"))
      (node (ref "IC15") (pin "38") (pinfunction "OVSS0_38") (pintype "passive"))
      (node (ref "IC15") (pin "5") (pinfunction "VSSA_PLL_5") (pintype "passive"))
      (node (ref "IC15") (pin "8") (pinfunction "VSS_PLL_8") (pintype "passive"))
      (node (ref "IC15") (pin "EXP") (pinfunction "EX-PAD_EXP") (pintype "passive"))
      (node (ref "IC16") (pin "12") (pinfunction "DVSS_12") (pintype "passive"))
      (node (ref "IC16") (pin "23") (pinfunction "OVSS1_23") (pintype "passive"))
      (node (ref "IC16") (pin "27") (pinfunction "DVSS_27") (pintype "passive"))
      (node (ref "IC16") (pin "38") (pinfunction "OVSS0_38") (pintype "passive"))
      (node (ref "IC16") (pin "5") (pinfunction "VSSA_PLL_5") (pintype "passive"))
      (node (ref "IC16") (pin "8") (pinfunction "VSS_PLL_8") (pintype "passive"))
      (node (ref "IC16") (pin "EXP") (pinfunction "EX-PAD_EXP") (pintype "passive"))
      (node (ref "IC17") (pin "12") (pinfunction "DVSS_12") (pintype "passive"))
      (node (ref "IC17") (pin "23") (pinfunction "OVSS1_23") (pintype "passive"))
      (node (ref "IC17") (pin "27") (pinfunction "DVSS_27") (pintype "passive"))
      (node (ref "IC17") (pin "38") (pinfunction "OVSS0_38") (pintype "passive"))
      (node (ref "IC17") (pin "5") (pinfunction "VSSA_PLL_5") (pintype "passive"))
      (node (ref "IC17") (pin "8") (pinfunction "VSS_PLL_8") (pintype "passive"))
      (node (ref "IC17") (pin "EXP") (pinfunction "EX-PAD_EXP") (pintype "passive"))
      (node (ref "IC19") (pin "12") (pinfunction "DVSS_12") (pintype "passive"))
      (node (ref "IC19") (pin "23") (pinfunction "OVSS1_23") (pintype "passive"))
      (node (ref "IC19") (pin "27") (pinfunction "DVSS_27") (pintype "passive"))
      (node (ref "IC19") (pin "38") (pinfunction "OVSS0_38") (pintype "passive"))
      (node (ref "IC19") (pin "5") (pinfunction "VSSA_PLL_5") (pintype "passive"))
      (node (ref "IC19") (pin "8") (pinfunction "VSS_PLL_8") (pintype "passive"))
      (node (ref "IC19") (pin "EXP") (pinfunction "EX-PAD_EXP") (pintype "passive"))
      (node (ref "IC2") (pin "4") (pinfunction "GND_4") (pintype "passive"))
      (node (ref "IC20") (pin "12") (pinfunction "DVSS_12") (pintype "passive"))
      (node (ref "IC20") (pin "23") (pinfunction "OVSS1_23") (pintype "passive"))
      (node (ref "IC20") (pin "27") (pinfunction "DVSS_27") (pintype "passive"))
      (node (ref "IC20") (pin "38") (pinfunction "OVSS0_38") (pintype "passive"))
      (node (ref "IC20") (pin "5") (pinfunction "VSSA_PLL_5") (pintype "passive"))
      (node (ref "IC20") (pin "8") (pinfunction "VSS_PLL_8") (pintype "passive"))
      (node (ref "IC20") (pin "EXP") (pinfunction "EX-PAD_EXP") (pintype "passive"))
      (node (ref "IC3") (pin "3") (pinfunction "GND_3") (pintype "power_in"))
      (node (ref "IC3") (pin "5") (pinfunction "EN_5") (pintype "input"))
      (node (ref "IC3") (pin "6") (pinfunction "GND_6") (pintype "power_in"))
      (node (ref "IC4") (pin "20") (pinfunction "GND_20") (pintype "passive"))
      (node (ref "IC5") (pin "7") (pinfunction "GND_7") (pintype "power_in"))
      (node (ref "IC6") (pin "12") (pinfunction "DVSS_12") (pintype "passive"))
      (node (ref "IC6") (pin "23") (pinfunction "OVSS1_23") (pintype "passive"))
      (node (ref "IC6") (pin "27") (pinfunction "DVSS_27") (pintype "passive"))
      (node (ref "IC6") (pin "38") (pinfunction "OVSS0_38") (pintype "passive"))
      (node (ref "IC6") (pin "5") (pinfunction "VSSA_PLL_5") (pintype "passive"))
      (node (ref "IC6") (pin "8") (pinfunction "VSS_PLL_8") (pintype "passive"))
      (node (ref "IC6") (pin "EXP") (pinfunction "EX-PAD_EXP") (pintype "passive"))
      (node (ref "IC7") (pin "12") (pinfunction "DVSS_12") (pintype "passive"))
      (node (ref "IC7") (pin "23") (pinfunction "OVSS1_23") (pintype "passive"))
      (node (ref "IC7") (pin "27") (pinfunction "DVSS_27") (pintype "passive"))
      (node (ref "IC7") (pin "38") (pinfunction "OVSS0_38") (pintype "passive"))
      (node (ref "IC7") (pin "5") (pinfunction "VSSA_PLL_5") (pintype "passive"))
      (node (ref "IC7") (pin "8") (pinfunction "VSS_PLL_8") (pintype "passive"))
      (node (ref "IC7") (pin "EXP") (pinfunction "EX-PAD_EXP") (pintype "passive"))
      (node (ref "IC8") (pin "12") (pinfunction "DVSS_12") (pintype "passive"))
      (node (ref "IC8") (pin "23") (pinfunction "OVSS1_23") (pintype "passive"))
      (node (ref "IC8") (pin "27") (pinfunction "DVSS_27") (pintype "passive"))
      (node (ref "IC8") (pin "38") (pinfunction "OVSS0_38") (pintype "passive"))
      (node (ref "IC8") (pin "5") (pinfunction "VSSA_PLL_5") (pintype "passive"))
      (node (ref "IC8") (pin "8") (pinfunction "VSS_PLL_8") (pintype "passive"))
      (node (ref "IC8") (pin "EXP") (pinfunction "EX-PAD_EXP") (pintype "passive"))
      (node (ref "IC9") (pin "12") (pinfunction "DVSS_12") (pintype "passive"))
      (node (ref "IC9") (pin "23") (pinfunction "OVSS1_23") (pintype "passive"))
      (node (ref "IC9") (pin "27") (pinfunction "DVSS_27") (pintype "passive"))
      (node (ref "IC9") (pin "38") (pinfunction "OVSS0_38") (pintype "passive"))
      (node (ref "IC9") (pin "5") (pinfunction "VSSA_PLL_5") (pintype "passive"))
      (node (ref "IC9") (pin "8") (pinfunction "VSS_PLL_8") (pintype "passive"))
      (node (ref "IC9") (pin "EXP") (pinfunction "EX-PAD_EXP") (pintype "passive"))
      (node (ref "LED1") (pin "C") (pinfunction "C_C") (pintype "passive"))
      (node (ref "Q1") (pin "2") (pinfunction "GND_2") (pintype "power_in"))
      (node (ref "Q2") (pin "2") (pinfunction "S_2") (pintype "passive"))
      (node (ref "R13") (pin "2") (pinfunction "2_2") (pintype "passive"))
      (node (ref "R14") (pin "2") (pinfunction "2_2") (pintype "passive"))
      (node (ref "R3") (pin "2") (pinfunction "2_2") (pintype "passive"))
      (node (ref "R3") (pin "3") (pinfunction "3_3") (pintype "passive"))
      (node (ref "TP9") (pin "TP") (pinfunction "TP_TP") (pintype "input"))
      (node (ref "U$1") (pin "1") (pinfunction "GND_1") (pintype "bidirectional"))
      (node (ref "X1") (pin "4") (pinfunction "GND_4") (pintype "passive"))
      (node (ref "X1") (pin "5") (pinfunction "GND_5") (pintype "passive"))
      (node (ref "X1") (pin "6") (pinfunction "GND_6") (pintype "passive"))
      (node (ref "X2") (pin "3") (pinfunction "3_3") (pintype "passive"))
      (node (ref "X4") (pin "5") (pinfunction "5_5") (pintype "passive"))
      (node (ref "X4") (pin "M1") (pinfunction "S1_M1") (pintype "passive"))
      (node (ref "X4") (pin "M2") (pinfunction "S2_M2") (pintype "passive"))
      (node (ref "X4") (pin "M3") (pinfunction "S3_M3") (pintype "passive"))
      (node (ref "X4") (pin "M4") (pinfunction "S4_M4") (pintype "passive"))
    )
    (net (code "20") (name "ICSPCLK") (class "Default")
      (node (ref "IC4") (pin "15") (pinfunction "RC1/ICSPCLK_15") (pintype "passive"))
      (node (ref "X2") (pin "5") (pinfunction "5_5") (pintype "passive"))
    )
    (net (code "21") (name "ICSPDAT") (class "Default")
      (node (ref "IC4") (pin "16") (pinfunction "RC0/ICSPDAT_16") (pintype "passive"))
      (node (ref "X2") (pin "4") (pinfunction "4_4") (pintype "passive"))
    )
    (net (code "22") (name "LED") (class "Default")
      (node (ref "IC4") (pin "2") (pinfunction "RA5_2") (pintype "passive"))
      (node (ref "R9") (pin "2") (pinfunction "2_2") (pintype "passive"))
    )
    (net (code "23") (name "N$11") (class "Default")
      (node (ref "U$1") (pin "12") (pinfunction "D7_12") (pintype "bidirectional"))
    )
    (net (code "24") (name "N$12") (class "Default")
      (node (ref "U$1") (pin "11") (pinfunction "D8_11") (pintype "bidirectional"))
    )
    (net (code "25") (name "N$13") (class "Default")
      (node (ref "U$1") (pin "9") (pinfunction "S7_9") (pintype "bidirectional"))
    )
    (net (code "26") (name "N$14") (class "Default")
      (node (ref "U$1") (pin "10") (pinfunction "S8_10") (pintype "bidirectional"))
    )
    (net (code "27") (name "NTC") (class "Default")
      (node (ref "IC4") (pin "14") (pinfunction "RC2_14") (pintype "passive"))
      (node (ref "R14") (pin "1") (pinfunction "1_1") (pintype "passive"))
      (node (ref "RT1") (pin "1") (pinfunction "1_1") (pintype "passive"))
    )
    (net (code "28") (name "Net-(IC1-ADJ)") (class "Default")
      (node (ref "IC1") (pin "17") (pinfunction "ADJ_17") (pintype "passive"))
      (node (ref "R2") (pin "1") (pinfunction "1_1") (pintype "passive"))
    )
    (net (code "29") (name "Net-(IC1-SENSE+)") (class "Default")
      (node (ref "IC1") (pin "11") (pinfunction "SENSE+_11") (pintype "passive"))
      (node (ref "R1") (pin "1") (pinfunction "1_1") (pintype "passive"))
      (node (ref "TP1") (pin "TP") (pinfunction "TP_TP") (pintype "input"))
    )
    (net (code "30") (name "Net-(IC2-IN)") (class "Default")
      (node (ref "IC2") (pin "5") (pinfunction "IN_5") (pintype "passive"))
      (node (ref "Q1") (pin "3") (pinfunction "OUT_3") (pintype "output"))
    )
    (net (code "31") (name "Net-(IC3-OUT)") (class "Default")
      (node (ref "D1") (pin "C") (pinfunction "C_C") (pintype "passive"))
      (node (ref "IC3") (pin "2") (pinfunction "OUT_2") (pintype "output"))
      (node (ref "L1") (pin "1") (pinfunction "1_1") (pintype "passive"))
    )
    (net (code "32") (name "Net-(IC4-VCC_USB)") (class "Default")
      (node (ref "C16") (pin "2") (pinfunction "2_2") (pintype "passive"))
      (node (ref "IC4") (pin "17") (pinfunction "VCC_USB_17") (pintype "passive"))
    )
    (net (code "33") (name "Net-(IC5A-I0)") (class "Default")
      (node (ref "IC5") (pin "2") (pinfunction "I0_2") (pintype "input"))
      (node (ref "IC5") (pin "3") (pinfunction "I1_3") (pintype "input"))
      (node (ref "IC5") (pin "4") (pinfunction "O_4") (pintype "output"))
    )
    (net (code "34") (name "Net-(IC5B-I0)") (class "Default")
      (node (ref "IC5") (pin "13") (pinfunction "O_13") (pintype "output"))
      (node (ref "IC5") (pin "5") (pinfunction "I0_5") (pintype "input"))
      (node (ref "R8") (pin "1") (pinfunction "1_1") (pintype "passive"))
    )
    (net (code "35") (name "Net-(IC5B-I1)") (class "Default")
      (node (ref "C17") (pin "2") (pinfunction "2_2") (pintype "passive"))
      (node (ref "IC5") (pin "6") (pinfunction "I1_6") (pintype "input"))
      (node (ref "R8") (pin "2") (pinfunction "2_2") (pintype "passive"))
    )
    (net (code "36") (name "Net-(IC6-CONFIG_NO)") (class "Default")
      (node (ref "IC6") (pin "35") (pinfunction "CONFIG_NO_35") (pintype "passive"))
      (node (ref "IC7") (pin "2") (pinfunction "CONFIG_NI_2") (pintype "passive"))
    )
    (net (code "37") (name "Net-(IC6-CONFIG_PO)") (class "Default")
      (node (ref "IC6") (pin "36") (pinfunction "CONFIG_PO_36") (pintype "passive"))
      (node (ref "IC7") (pin "1") (pinfunction "CONFIG_PI_1") (pintype "passive"))
    )
    (net (code "38") (name "Net-(IC6-RSTN)") (class "Default")
      (node (ref "C26") (pin "2") (pinfunction "2_2") (pintype "passive"))
      (node (ref "IC6") (pin "44") (pinfunction "RSTN_44") (pintype "passive"))
      (node (ref "R15") (pin "2") (pinfunction "2_2") (pintype "passive"))
    )
    (net (code "39") (name "Net-(IC6-VDDA_PLL)") (class "Default")
      (node (ref "C25") (pin "1") (pinfunction "1_1") (pintype "passive"))
      (node (ref "IC6") (pin "6") (pinfunction "VDDA_PLL_6") (pintype "passive"))
      (node (ref "IC6") (pin "7") (pinfunction "VDD_PLL_7") (pintype "passive"))
      (node (ref "L2") (pin "2") (pinfunction "2_2") (pintype "passive"))
    )
    (net (code "40") (name "Net-(IC7-CONFIG_NO)") (class "Default")
      (node (ref "IC7") (pin "35") (pinfunction "CONFIG_NO_35") (pintype "passive"))
      (node (ref "IC8") (pin "2") (pinfunction "CONFIG_NI_2") (pintype "passive"))
    )
    (net (code "41") (name "Net-(IC7-CONFIG_PO)") (class "Default")
      (node (ref "IC7") (pin "36") (pinfunction "CONFIG_PO_36") (pintype "passive"))
      (node (ref "IC8") (pin "1") (pinfunction "CONFIG_PI_1") (pintype "passive"))
    )
    (net (code "42") (name "Net-(IC7-RSTN)") (class "Default")
      (node (ref "C27") (pin "2") (pinfunction "2_2") (pintype "passive"))
      (node (ref "IC7") (pin "44") (pinfunction "RSTN_44") (pintype "passive"))
      (node (ref "R16") (pin "2") (pinfunction "2_2") (pintype "passive"))
    )
    (net (code "43") (name "Net-(IC7-VDDA_PLL)") (class "Default")
      (node (ref "C28") (pin "1") (pinfunction "1_1") (pintype "passive"))
      (node (ref "IC7") (pin "6") (pinfunction "VDDA_PLL_6") (pintype "passive"))
      (node (ref "IC7") (pin "7") (pinfunction "VDD_PLL_7") (pintype "passive"))
      (node (ref "L3") (pin "2") (pinfunction "2_2") (pintype "passive"))
    )
    (net (code "44") (name "Net-(IC8-CONFIG_NO)") (class "Default")
      (node (ref "IC8") (pin "35") (pinfunction "CONFIG_NO_35") (pintype "passive"))
      (node (ref "IC9") (pin "2") (pinfunction "CONFIG_NI_2") (pintype "passive"))
    )
    (net (code "45") (name "Net-(IC8-CONFIG_PO)") (class "Default")
      (node (ref "IC8") (pin "36") (pinfunction "CONFIG_PO_36") (pintype "passive"))
      (node (ref "IC9") (pin "1") (pinfunction "CONFIG_PI_1") (pintype "passive"))
    )
    (net (code "46") (name "Net-(IC8-RSTN)") (class "Default")
      (node (ref "C36") (pin "2") (pinfunction "2_2") (pintype "passive"))
      (node (ref "IC8") (pin "44") (pinfunction "RSTN_44") (pintype "passive"))
      (node (ref "R17") (pin "2") (pinfunction "2_2") (pintype "passive"))
    )
    (net (code "47") (name "Net-(IC8-VDDA_PLL)") (class "Default")
      (node (ref "C37") (pin "1") (pinfunction "1_1") (pintype "passive"))
      (node (ref "IC8") (pin "6") (pinfunction "VDDA_PLL_6") (pintype "passive"))
      (node (ref "IC8") (pin "7") (pinfunction "VDD_PLL_7") (pintype "passive"))
      (node (ref "L4") (pin "2") (pinfunction "2_2") (pintype "passive"))
    )
    (net (code "48") (name "Net-(IC9-RSTN)") (class "Default")
      (node (ref "C45") (pin "2") (pinfunction "2_2") (pintype "passive"))
      (node (ref "IC9") (pin "44") (pinfunction "RSTN_44") (pintype "passive"))
      (node (ref "R18") (pin "2") (pinfunction "2_2") (pintype "passive"))
    )
    (net (code "49") (name "Net-(IC9-VDDA_PLL)") (class "Default")
      (node (ref "C46") (pin "1") (pinfunction "1_1") (pintype "passive"))
      (node (ref "IC9") (pin "6") (pinfunction "VDDA_PLL_6") (pintype "passive"))
      (node (ref "IC9") (pin "7") (pinfunction "VDD_PLL_7") (pintype "passive"))
      (node (ref "L5") (pin "2") (pinfunction "2_2") (pintype "passive"))
    )
    (net (code "50") (name "Net-(IC10-CONFIG_NI)") (class "Default")
      (node (ref "IC10") (pin "2") (pinfunction "CONFIG_NI_2") (pintype "passive"))
      (node (ref "IC9") (pin "35") (pinfunction "CONFIG_NO_35") (pintype "passive"))
    )
    (net (code "51") (name "Net-(IC10-CONFIG_NO)") (class "Default")
      (node (ref "IC10") (pin "35") (pinfunction "CONFIG_NO_35") (pintype "passive"))
      (node (ref "IC19") (pin "2") (pinfunction "CONFIG_NI_2") (pintype "passive"))
    )
    (net (code "52") (name "Net-(IC10-CONFIG_PI)") (class "Default")
      (node (ref "IC10") (pin "1") (pinfunction "CONFIG_PI_1") (pintype "passive"))
      (node (ref "IC9") (pin "36") (pinfunction "CONFIG_PO_36") (pintype "passive"))
    )
    (net (code "53") (name "Net-(IC10-CONFIG_PO)") (class "Default")
      (node (ref "IC10") (pin "36") (pinfunction "CONFIG_PO_36") (pintype "passive"))
      (node (ref "IC19") (pin "1") (pinfunction "CONFIG_PI_1") (pintype "passive"))
    )
    (net (code "54") (name "Net-(IC10-RSTN)") (class "Default")
      (node (ref "C54") (pin "2") (pinfunction "2_2") (pintype "passive"))
      (node (ref "IC10") (pin "44") (pinfunction "RSTN_44") (pintype "passive"))
      (node (ref "R19") (pin "2") (pinfunction "2_2") (pintype "passive"))
    )
    (net (code "55") (name "Net-(IC10-VDDA_PLL)") (class "Default")
      (node (ref "C55") (pin "1") (pinfunction "1_1") (pintype "passive"))
      (node (ref "IC10") (pin "6") (pinfunction "VDDA_PLL_6") (pintype "passive"))
      (node (ref "IC10") (pin "7") (pinfunction "VDD_PLL_7") (pintype "passive"))
      (node (ref "L6") (pin "2") (pinfunction "2_2") (pintype "passive"))
    )
    (net (code "56") (name "Net-(IC11-CONFIG_NO)") (class "Default")
      (node (ref "IC11") (pin "35") (pinfunction "CONFIG_NO_35") (pintype "passive"))
      (node (ref "IC12") (pin "2") (pinfunction "CONFIG_NI_2") (pintype "passive"))
    )
    (net (code "57") (name "Net-(IC11-CONFIG_PO)") (class "Default")
      (node (ref "IC11") (pin "36") (pinfunction "CONFIG_PO_36") (pintype "passive"))
      (node (ref "IC12") (pin "1") (pinfunction "CONFIG_PI_1") (pintype "passive"))
    )
    (net (code "58") (name "Net-(IC11-RSTN)") (class "Default")
      (node (ref "C63") (pin "2") (pinfunction "2_2") (pintype "passive"))
      (node (ref "IC11") (pin "44") (pinfunction "RSTN_44") (pintype "passive"))
      (node (ref "R20") (pin "2") (pinfunction "2_2") (pintype "passive"))
    )
    (net (code "59") (name "Net-(IC11-VDDA_PLL)") (class "Default")
      (node (ref "C64") (pin "1") (pinfunction "1_1") (pintype "passive"))
      (node (ref "IC11") (pin "6") (pinfunction "VDDA_PLL_6") (pintype "passive"))
      (node (ref "IC11") (pin "7") (pinfunction "VDD_PLL_7") (pintype "passive"))
      (node (ref "L7") (pin "2") (pinfunction "2_2") (pintype "passive"))
    )
    (net (code "60") (name "Net-(IC12-CONFIG_NO)") (class "Default")
      (node (ref "IC12") (pin "35") (pinfunction "CONFIG_NO_35") (pintype "passive"))
      (node (ref "IC13") (pin "2") (pinfunction "CONFIG_NI_2") (pintype "passive"))
    )
    (net (code "61") (name "Net-(IC12-CONFIG_PO)") (class "Default")
      (node (ref "IC12") (pin "36") (pinfunction "CONFIG_PO_36") (pintype "passive"))
      (node (ref "IC13") (pin "1") (pinfunction "CONFIG_PI_1") (pintype "passive"))
    )
    (net (code "62") (name "Net-(IC12-RSTN)") (class "Default")
      (node (ref "C72") (pin "2") (pinfunction "2_2") (pintype "passive"))
      (node (ref "IC12") (pin "44") (pinfunction "RSTN_44") (pintype "passive"))
      (node (ref "R21") (pin "2") (pinfunction "2_2") (pintype "passive"))
    )
    (net (code "63") (name "Net-(IC12-VDDA_PLL)") (class "Default")
      (node (ref "C73") (pin "1") (pinfunction "1_1") (pintype "passive"))
      (node (ref "IC12") (pin "6") (pinfunction "VDDA_PLL_6") (pintype "passive"))
      (node (ref "IC12") (pin "7") (pinfunction "VDD_PLL_7") (pintype "passive"))
      (node (ref "L8") (pin "2") (pinfunction "2_2") (pintype "passive"))
    )
    (net (code "64") (name "Net-(IC13-CONFIG_NO)") (class "Default")
      (node (ref "IC13") (pin "35") (pinfunction "CONFIG_NO_35") (pintype "passive"))
      (node (ref "IC14") (pin "2") (pinfunction "CONFIG_NI_2") (pintype "passive"))
    )
    (net (code "65") (name "Net-(IC13-CONFIG_PO)") (class "Default")
      (node (ref "IC13") (pin "36") (pinfunction "CONFIG_PO_36") (pintype "passive"))
      (node (ref "IC14") (pin "1") (pinfunction "CONFIG_PI_1") (pintype "passive"))
    )
    (net (code "66") (name "Net-(IC13-RSTN)") (class "Default")
      (node (ref "C81") (pin "2") (pinfunction "2_2") (pintype "passive"))
      (node (ref "IC13") (pin "44") (pinfunction "RSTN_44") (pintype "passive"))
      (node (ref "R22") (pin "2") (pinfunction "2_2") (pintype "passive"))
    )
    (net (code "67") (name "Net-(IC13-VDDA_PLL)") (class "Default")
      (node (ref "C82") (pin "1") (pinfunction "1_1") (pintype "passive"))
      (node (ref "IC13") (pin "6") (pinfunction "VDDA_PLL_6") (pintype "passive"))
      (node (ref "IC13") (pin "7") (pinfunction "VDD_PLL_7") (pintype "passive"))
      (node (ref "L9") (pin "2") (pinfunction "2_2") (pintype "passive"))
    )
    (net (code "68") (name "Net-(IC14-CONFIG_NO)") (class "Default")
      (node (ref "IC14") (pin "35") (pinfunction "CONFIG_NO_35") (pintype "passive"))
      (node (ref "IC15") (pin "2") (pinfunction "CONFIG_NI_2") (pintype "passive"))
    )
    (net (code "69") (name "Net-(IC14-CONFIG_PO)") (class "Default")
      (node (ref "IC14") (pin "36") (pinfunction "CONFIG_PO_36") (pintype "passive"))
      (node (ref "IC15") (pin "1") (pinfunction "CONFIG_PI_1") (pintype "passive"))
    )
    (net (code "70") (name "Net-(IC14-RSTN)") (class "Default")
      (node (ref "C90") (pin "2") (pinfunction "2_2") (pintype "passive"))
      (node (ref "IC14") (pin "44") (pinfunction "RSTN_44") (pintype "passive"))
      (node (ref "R23") (pin "2") (pinfunction "2_2") (pintype "passive"))
    )
    (net (code "71") (name "Net-(IC14-VDDA_PLL)") (class "Default")
      (node (ref "C91") (pin "1") (pinfunction "1_1") (pintype "passive"))
      (node (ref "IC14") (pin "6") (pinfunction "VDDA_PLL_6") (pintype "passive"))
      (node (ref "IC14") (pin "7") (pinfunction "VDD_PLL_7") (pintype "passive"))
      (node (ref "L10") (pin "2") (pinfunction "2_2") (pintype "passive"))
    )
    (net (code "72") (name "Net-(IC15-CONFIG_NO)") (class "Default")
      (node (ref "IC15") (pin "35") (pinfunction "CONFIG_NO_35") (pintype "passive"))
      (node (ref "IC16") (pin "2") (pinfunction "CONFIG_NI_2") (pintype "passive"))
    )
    (net (code "73") (name "Net-(IC15-CONFIG_PO)") (class "Default")
      (node (ref "IC15") (pin "36") (pinfunction "CONFIG_PO_36") (pintype "passive"))
      (node (ref "IC16") (pin "1") (pinfunction "CONFIG_PI_1") (pintype "passive"))
    )
    (net (code "74") (name "Net-(IC15-RSTN)") (class "Default")
      (node (ref "C99") (pin "2") (pinfunction "2_2") (pintype "passive"))
      (node (ref "IC15") (pin "44") (pinfunction "RSTN_44") (pintype "passive"))
      (node (ref "R24") (pin "2") (pinfunction "2_2") (pintype "passive"))
    )
    (net (code "75") (name "Net-(IC15-VDDA_PLL)") (class "Default")
      (node (ref "C100") (pin "1") (pinfunction "1_1") (pintype "passive"))
      (node (ref "IC15") (pin "6") (pinfunction "VDDA_PLL_6") (pintype "passive"))
      (node (ref "IC15") (pin "7") (pinfunction "VDD_PLL_7") (pintype "passive"))
      (node (ref "L11") (pin "2") (pinfunction "2_2") (pintype "passive"))
    )
    (net (code "76") (name "Net-(IC16-CONFIG_NO)") (class "Default")
      (node (ref "IC16") (pin "35") (pinfunction "CONFIG_NO_35") (pintype "passive"))
      (node (ref "IC17") (pin "2") (pinfunction "CONFIG_NI_2") (pintype "passive"))
    )
    (net (code "77") (name "Net-(IC16-CONFIG_PO)") (class "Default")
      (node (ref "IC16") (pin "36") (pinfunction "CONFIG_PO_36") (pintype "passive"))
      (node (ref "IC17") (pin "1") (pinfunction "CONFIG_PI_1") (pintype "passive"))
    )
    (net (code "78") (name "Net-(IC16-RSTN)") (class "Default")
      (node (ref "C12") (pin "2") (pinfunction "2_2") (pintype "passive"))
      (node (ref "IC16") (pin "44") (pinfunction "RSTN_44") (pintype "passive"))
      (node (ref "R25") (pin "2") (pinfunction "2_2") (pintype "passive"))
    )
    (net (code "79") (name "Net-(IC16-VDDA_PLL)") (class "Default")
      (node (ref "C108") (pin "1") (pinfunction "1_1") (pintype "passive"))
      (node (ref "IC16") (pin "6") (pinfunction "VDDA_PLL_6") (pintype "passive"))
      (node (ref "IC16") (pin "7") (pinfunction "VDD_PLL_7") (pintype "passive"))
      (node (ref "L12") (pin "2") (pinfunction "2_2") (pintype "passive"))
    )
    (net (code "80") (name "Net-(IC17-RSTN)") (class "Default")
      (node (ref "C116") (pin "2") (pinfunction "2_2") (pintype "passive"))
      (node (ref "IC17") (pin "44") (pinfunction "RSTN_44") (pintype "passive"))
      (node (ref "R26") (pin "2") (pinfunction "2_2") (pintype "passive"))
    )
    (net (code "81") (name "Net-(IC17-VDDA_PLL)") (class "Default")
      (node (ref "C117") (pin "1") (pinfunction "1_1") (pintype "passive"))
      (node (ref "IC17") (pin "6") (pinfunction "VDDA_PLL_6") (pintype "passive"))
      (node (ref "IC17") (pin "7") (pinfunction "VDD_PLL_7") (pintype "passive"))
      (node (ref "L13") (pin "2") (pinfunction "2_2") (pintype "passive"))
    )
    (net (code "82") (name "Net-(IC19-CONFIG_NO)") (class "Default")
      (node (ref "IC19") (pin "35") (pinfunction "CONFIG_NO_35") (pintype "passive"))
      (node (ref "IC20") (pin "2") (pinfunction "CONFIG_NI_2") (pintype "passive"))
    )
    (net (code "83") (name "Net-(IC19-CONFIG_PO)") (class "Default")
      (node (ref "IC19") (pin "36") (pinfunction "CONFIG_PO_36") (pintype "passive"))
      (node (ref "IC20") (pin "1") (pinfunction "CONFIG_PI_1") (pintype "passive"))
    )
    (net (code "84") (name "Net-(IC19-RSTN)") (class "Default")
      (node (ref "C134") (pin "2") (pinfunction "2_2") (pintype "passive"))
      (node (ref "IC19") (pin "44") (pinfunction "RSTN_44") (pintype "passive"))
      (node (ref "R28") (pin "2") (pinfunction "2_2") (pintype "passive"))
    )
    (net (code "85") (name "Net-(IC19-VDDA_PLL)") (class "Default")
      (node (ref "C135") (pin "1") (pinfunction "1_1") (pintype "passive"))
      (node (ref "IC19") (pin "6") (pinfunction "VDDA_PLL_6") (pintype "passive"))
      (node (ref "IC19") (pin "7") (pinfunction "VDD_PLL_7") (pintype "passive"))
      (node (ref "L15") (pin "2") (pinfunction "2_2") (pintype "passive"))
    )
    (net (code "86") (name "Net-(IC20-CONFIG_PO)") (class "Default")
      (node (ref "IC20") (pin "36") (pinfunction "CONFIG_PO_36") (pintype "passive"))
      (node (ref "TP2") (pin "TP") (pinfunction "TP_TP") (pintype "input"))
    )
    (net (code "87") (name "Net-(IC20-RSTN)") (class "Default")
      (node (ref "C143") (pin "2") (pinfunction "2_2") (pintype "passive"))
      (node (ref "IC20") (pin "44") (pinfunction "RSTN_44") (pintype "passive"))
      (node (ref "R29") (pin "2") (pinfunction "2_2") (pintype "passive"))
    )
    (net (code "88") (name "Net-(IC20-VDDA_PLL)") (class "Default")
      (node (ref "C144") (pin "1") (pinfunction "1_1") (pintype "passive"))
      (node (ref "IC20") (pin "6") (pinfunction "VDDA_PLL_6") (pintype "passive"))
      (node (ref "IC20") (pin "7") (pinfunction "VDD_PLL_7") (pintype "passive"))
      (node (ref "L16") (pin "2") (pinfunction "2_2") (pintype "passive"))
    )
    (net (code "89") (name "Net-(LED1-PadA)") (class "Default")
      (node (ref "LED1") (pin "A") (pinfunction "A_A") (pintype "passive"))
      (node (ref "R9") (pin "1") (pinfunction "1_1") (pintype "passive"))
    )
    (net (code "90") (name "Net-(Q2-D)") (class "Default")
      (node (ref "D2") (pin "A") (pinfunction "A_A") (pintype "passive"))
      (node (ref "Q2") (pin "3") (pinfunction "D_3") (pintype "passive"))
      (node (ref "X3") (pin "1") (pinfunction "GND_1") (pintype "passive"))
    )
    (net (code "91") (name "Net-(Q2-G)") (class "Default")
      (node (ref "Q2") (pin "1") (pinfunction "G_1") (pintype "passive"))
      (node (ref "R12") (pin "2") (pinfunction "2_2") (pintype "passive"))
      (node (ref "R13") (pin "1") (pinfunction "1_1") (pintype "passive"))
    )
    (net (code "92") (name "Net-(R2-Pad2)") (class "Default")
      (node (ref "R2") (pin "2") (pinfunction "2_2") (pintype "passive"))
      (node (ref "R3") (pin "1") (pinfunction "1_1") (pintype "passive"))
    )
    (net (code "93") (name "Net-(X3-TACHO)") (class "Default")
      (node (ref "R4") (pin "2") (pinfunction "2_2") (pintype "passive"))
      (node (ref "R7") (pin "2") (pinfunction "2_2") (pintype "passive"))
      (node (ref "X3") (pin "3") (pinfunction "TACHO_3") (pintype "passive"))
    )
    (net (code "94") (name "OSC_EN") (class "Default")
      (node (ref "IC4") (pin "3") (pinfunction "RA4_3") (pintype "passive"))
      (node (ref "Q1") (pin "1") (pinfunction "TS_1") (pintype "passive"))
    )
    (net (code "95") (name "REPORT_1V8_N") (class "Default")
      (node (ref "U$1") (pin "8") (pinfunction "S6_8") (pintype "bidirectional"))
    )
    (net (code "96") (name "REPORT_1V8_P") (class "Default")
      (node (ref "U$1") (pin "7") (pinfunction "S5_7") (pintype "bidirectional"))
    )
    (net (code "97") (name "REPORT_CLK") (class "Default")
      (node (ref "IC4") (pin "10") (pinfunction "RB7_10") (pintype "passive"))
      (node (ref "IC5") (pin "1") (pinfunction "O_1") (pintype "output"))
    )
    (net (code "98") (name "REPORT_DATA") (class "Default")
      (node (ref "IC4") (pin "12") (pinfunction "RB5_12") (pintype "passive"))
      (node (ref "IC5") (pin "10") (pinfunction "O_10") (pintype "output"))
    )
    (net (code "99") (name "REPORT_N") (class "Default")
      (node (ref "IC10") (pin "16") (pinfunction "REPORT_N_16") (pintype "passive"))
      (node (ref "IC11") (pin "16") (pinfunction "REPORT_N_16") (pintype "passive"))
      (node (ref "IC12") (pin "16") (pinfunction "REPORT_N_16") (pintype "passive"))
      (node (ref "IC13") (pin "16") (pinfunction "REPORT_N_16") (pintype "passive"))
      (node (ref "IC14") (pin "16") (pinfunction "REPORT_N_16") (pintype "passive"))
      (node (ref "IC15") (pin "16") (pinfunction "REPORT_N_16") (pintype "passive"))
      (node (ref "IC16") (pin "16") (pinfunction "REPORT_N_16") (pintype "passive"))
      (node (ref "IC17") (pin "16") (pinfunction "REPORT_N_16") (pintype "passive"))
      (node (ref "IC19") (pin "16") (pinfunction "REPORT_N_16") (pintype "passive"))
      (node (ref "IC20") (pin "16") (pinfunction "REPORT_N_16") (pintype "passive"))
      (node (ref "IC5") (pin "12") (pinfunction "I1_12") (pintype "input"))
      (node (ref "IC5") (pin "8") (pinfunction "I0_8") (pintype "input"))
      (node (ref "IC5") (pin "9") (pinfunction "I1_9") (pintype "input"))
      (node (ref "IC6") (pin "16") (pinfunction "REPORT_N_16") (pintype "passive"))
      (node (ref "IC7") (pin "16") (pinfunction "REPORT_N_16") (pintype "passive"))
      (node (ref "IC8") (pin "16") (pinfunction "REPORT_N_16") (pintype "passive"))
      (node (ref "IC9") (pin "16") (pinfunction "REPORT_N_16") (pintype "passive"))
      (node (ref "R6") (pin "2") (pinfunction "2_2") (pintype "passive"))
      (node (ref "U$1") (pin "13") (pinfunction "D6_13") (pintype "bidirectional"))
    )
    (net (code "100") (name "REPORT_P") (class "Default")
      (node (ref "IC10") (pin "17") (pinfunction "REPORT_P_17") (pintype "passive"))
      (node (ref "IC11") (pin "17") (pinfunction "REPORT_P_17") (pintype "passive"))
      (node (ref "IC12") (pin "17") (pinfunction "REPORT_P_17") (pintype "passive"))
      (node (ref "IC13") (pin "17") (pinfunction "REPORT_P_17") (pintype "passive"))
      (node (ref "IC14") (pin "17") (pinfunction "REPORT_P_17") (pintype "passive"))
      (node (ref "IC15") (pin "17") (pinfunction "REPORT_P_17") (pintype "passive"))
      (node (ref "IC16") (pin "17") (pinfunction "REPORT_P_17") (pintype "passive"))
      (node (ref "IC17") (pin "17") (pinfunction "REPORT_P_17") (pintype "passive"))
      (node (ref "IC19") (pin "17") (pinfunction "REPORT_P_17") (pintype "passive"))
      (node (ref "IC20") (pin "17") (pinfunction "REPORT_P_17") (pintype "passive"))
      (node (ref "IC5") (pin "11") (pinfunction "I0_11") (pintype "input"))
      (node (ref "IC6") (pin "17") (pinfunction "REPORT_P_17") (pintype "passive"))
      (node (ref "IC7") (pin "17") (pinfunction "REPORT_P_17") (pintype "passive"))
      (node (ref "IC8") (pin "17") (pinfunction "REPORT_P_17") (pintype "passive"))
      (node (ref "IC9") (pin "17") (pinfunction "REPORT_P_17") (pintype "passive"))
      (node (ref "R5") (pin "2") (pinfunction "2_2") (pintype "passive"))
      (node (ref "U$1") (pin "14") (pinfunction "D5_14") (pintype "bidirectional"))
    )
    (net (code "101") (name "SCL") (class "Default")
      (node (ref "IC4") (pin "11") (pinfunction "RB6_11") (pintype "passive"))
      (node (ref "R11") (pin "2") (pinfunction "2_2") (pintype "passive"))
      (node (ref "TP7") (pin "TP") (pinfunction "TP_TP") (pintype "input"))
    )
    (net (code "102") (name "SDA") (class "Default")
      (node (ref "IC4") (pin "13") (pinfunction "RB4_13") (pintype "passive"))
      (node (ref "R10") (pin "2") (pinfunction "2_2") (pintype "passive"))
      (node (ref "TP8") (pin "TP") (pinfunction "TP_TP") (pintype "input"))
    )
    (net (code "103") (name "USB_DM") (class "Default")
      (node (ref "IC4") (pin "18") (pinfunction "RA1/D-_18") (pintype "passive"))
      (node (ref "X4") (pin "2") (pinfunction "2_2") (pintype "passive"))
    )
    (net (code "104") (name "USB_DP") (class "Default")
      (node (ref "IC4") (pin "19") (pinfunction "RA0/D+_19") (pintype "passive"))
      (node (ref "X4") (pin "3") (pinfunction "3_3") (pintype "passive"))
    )
    (net (code "105") (name "unconnected-(IC1-INH-Pad7)") (class "Default")
      (node (ref "IC1") (pin "7") (pinfunction "INH_7") (pintype "passive"))
    )
    (net (code "106") (name "unconnected-(IC1-MAR_DOWN-Pad20)") (class "Default")
      (node (ref "IC1") (pin "20") (pinfunction "MAR_DOWN_20") (pintype "passive"))
    )
    (net (code "107") (name "unconnected-(IC1-MAR_UP-Pad19)") (class "Default")
      (node (ref "IC1") (pin "19") (pinfunction "MAR_UP_19") (pintype "passive"))
    )
    (net (code "108") (name "unconnected-(IC1-UVLO-Pad8)") (class "Default")
      (node (ref "IC1") (pin "8") (pinfunction "UVLO_8") (pintype "passive"))
    )
    (net (code "109") (name "unconnected-(IC2-OUT3-Pad6)") (class "Default")
      (node (ref "IC2") (pin "6") (pinfunction "OUT3_6") (pintype "passive"))
    )
    (net (code "110") (name "unconnected-(IC2-OUT4-Pad7)") (class "Default")
      (node (ref "IC2") (pin "7") (pinfunction "OUT4_7") (pintype "passive"))
    )
    (net (code "111") (name "unconnected-(IC6-CORE_CLKOUT-Pad43)") (class "Default")
      (node (ref "IC6") (pin "43") (pinfunction "CORE_CLKOUT_43") (pintype "passive"))
    )
    (net (code "112") (name "unconnected-(IC7-CORE_CLKOUT-Pad43)") (class "Default")
      (node (ref "IC7") (pin "43") (pinfunction "CORE_CLKOUT_43") (pintype "passive"))
    )
    (net (code "113") (name "unconnected-(IC8-CORE_CLKOUT-Pad43)") (class "Default")
      (node (ref "IC8") (pin "43") (pinfunction "CORE_CLKOUT_43") (pintype "passive"))
    )
    (net (code "114") (name "unconnected-(IC9-CORE_CLKOUT-Pad43)") (class "Default")
      (node (ref "IC9") (pin "43") (pinfunction "CORE_CLKOUT_43") (pintype "passive"))
    )
    (net (code "115") (name "unconnected-(IC10-CORE_CLKOUT-Pad43)") (class "Default")
      (node (ref "IC10") (pin "43") (pinfunction "CORE_CLKOUT_43") (pintype "passive"))
    )
    (net (code "116") (name "unconnected-(IC11-CORE_CLKOUT-Pad43)") (class "Default")
      (node (ref "IC11") (pin "43") (pinfunction "CORE_CLKOUT_43") (pintype "passive"))
    )
    (net (code "117") (name "unconnected-(IC12-CORE_CLKOUT-Pad43)") (class "Default")
      (node (ref "IC12") (pin "43") (pinfunction "CORE_CLKOUT_43") (pintype "passive"))
    )
    (net (code "118") (name "unconnected-(IC13-CORE_CLKOUT-Pad43)") (class "Default")
      (node (ref "IC13") (pin "43") (pinfunction "CORE_CLKOUT_43") (pintype "passive"))
    )
    (net (code "119") (name "unconnected-(IC14-CORE_CLKOUT-Pad43)") (class "Default")
      (node (ref "IC14") (pin "43") (pinfunction "CORE_CLKOUT_43") (pintype "passive"))
    )
    (net (code "120") (name "unconnected-(IC15-CORE_CLKOUT-Pad43)") (class "Default")
      (node (ref "IC15") (pin "43") (pinfunction "CORE_CLKOUT_43") (pintype "passive"))
    )
    (net (code "121") (name "unconnected-(IC16-CORE_CLKOUT-Pad43)") (class "Default")
      (node (ref "IC16") (pin "43") (pinfunction "CORE_CLKOUT_43") (pintype "passive"))
    )
    (net (code "122") (name "unconnected-(IC17-CONFIG_NO-Pad35)") (class "Default")
      (node (ref "IC17") (pin "35") (pinfunction "CONFIG_NO_35") (pintype "passive"))
    )
    (net (code "123") (name "unconnected-(IC17-CONFIG_PO-Pad36)") (class "Default")
      (node (ref "IC17") (pin "36") (pinfunction "CONFIG_PO_36") (pintype "passive"))
    )
    (net (code "124") (name "unconnected-(IC17-CORE_CLKOUT-Pad43)") (class "Default")
      (node (ref "IC17") (pin "43") (pinfunction "CORE_CLKOUT_43") (pintype "passive"))
    )
    (net (code "125") (name "unconnected-(IC19-CORE_CLKOUT-Pad43)") (class "Default")
      (node (ref "IC19") (pin "43") (pinfunction "CORE_CLKOUT_43") (pintype "passive"))
    )
    (net (code "126") (name "unconnected-(IC20-CONFIG_NO-Pad35)") (class "Default")
      (node (ref "IC20") (pin "35") (pinfunction "CONFIG_NO_35") (pintype "passive"))
    )
    (net (code "127") (name "unconnected-(IC20-CORE_CLKOUT-Pad43)") (class "Default")
      (node (ref "IC20") (pin "43") (pinfunction "CORE_CLKOUT_43") (pintype "passive"))
    )
    (net (code "128") (name "unconnected-(TP3-PadTP)") (class "Default")
      (node (ref "TP3") (pin "TP") (pinfunction "TP_TP") (pintype "input"))
    )
    (net (code "129") (name "unconnected-(TP4-PadTP)") (class "Default")
      (node (ref "TP4") (pin "TP") (pinfunction "TP_TP") (pintype "input"))
    )
    (net (code "130") (name "unconnected-(TP5-PadTP)") (class "Default")
      (node (ref "TP5") (pin "TP") (pinfunction "TP_TP") (pintype "input"))
    )
    (net (code "131") (name "unconnected-(X2-Pad6)") (class "Default")
      (node (ref "X2") (pin "6") (pinfunction "6_6") (pintype "passive"))
    )
    (net (code "132") (name "unconnected-(X4-Pad1)") (class "Default")
      (node (ref "X4") (pin "1") (pinfunction "1_1") (pintype "passive"))
    )
    (net (code "133") (name "unconnected-(X4-Pad4)") (class "Default")
      (node (ref "X4") (pin "4") (pinfunction "4_4") (pintype "passive"))
    )
  )
)
